# motorko_cryo_drake.net
KiCad netlist of a schematic drawn in EasyEDA Pro
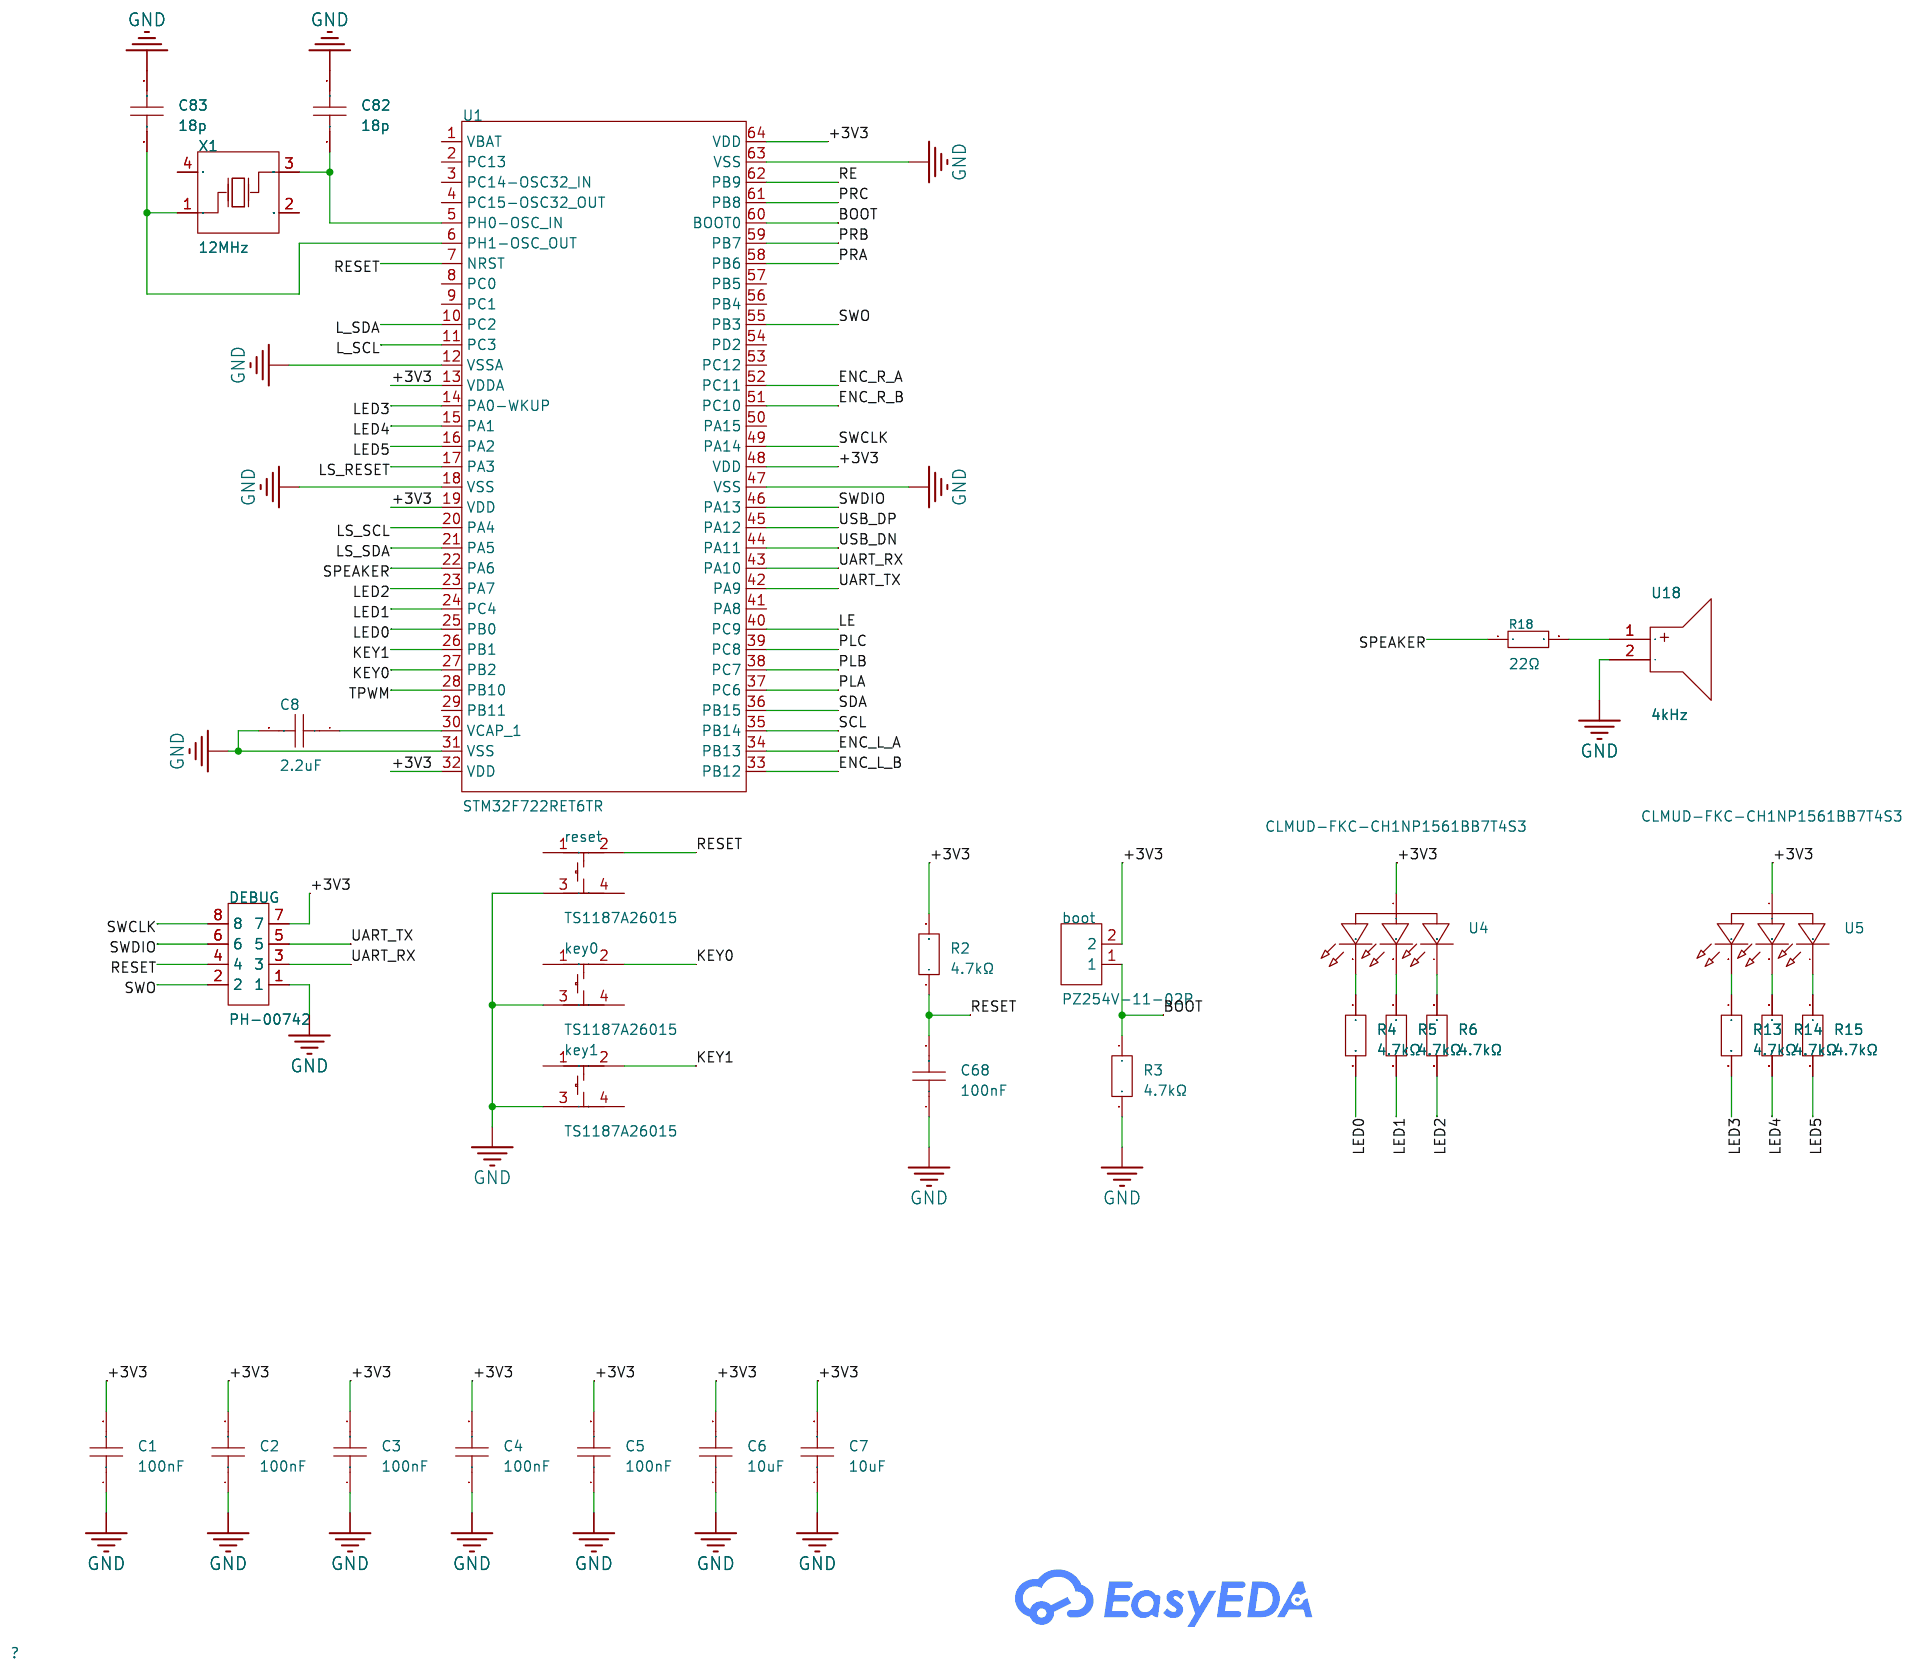
[diagram p0: main]
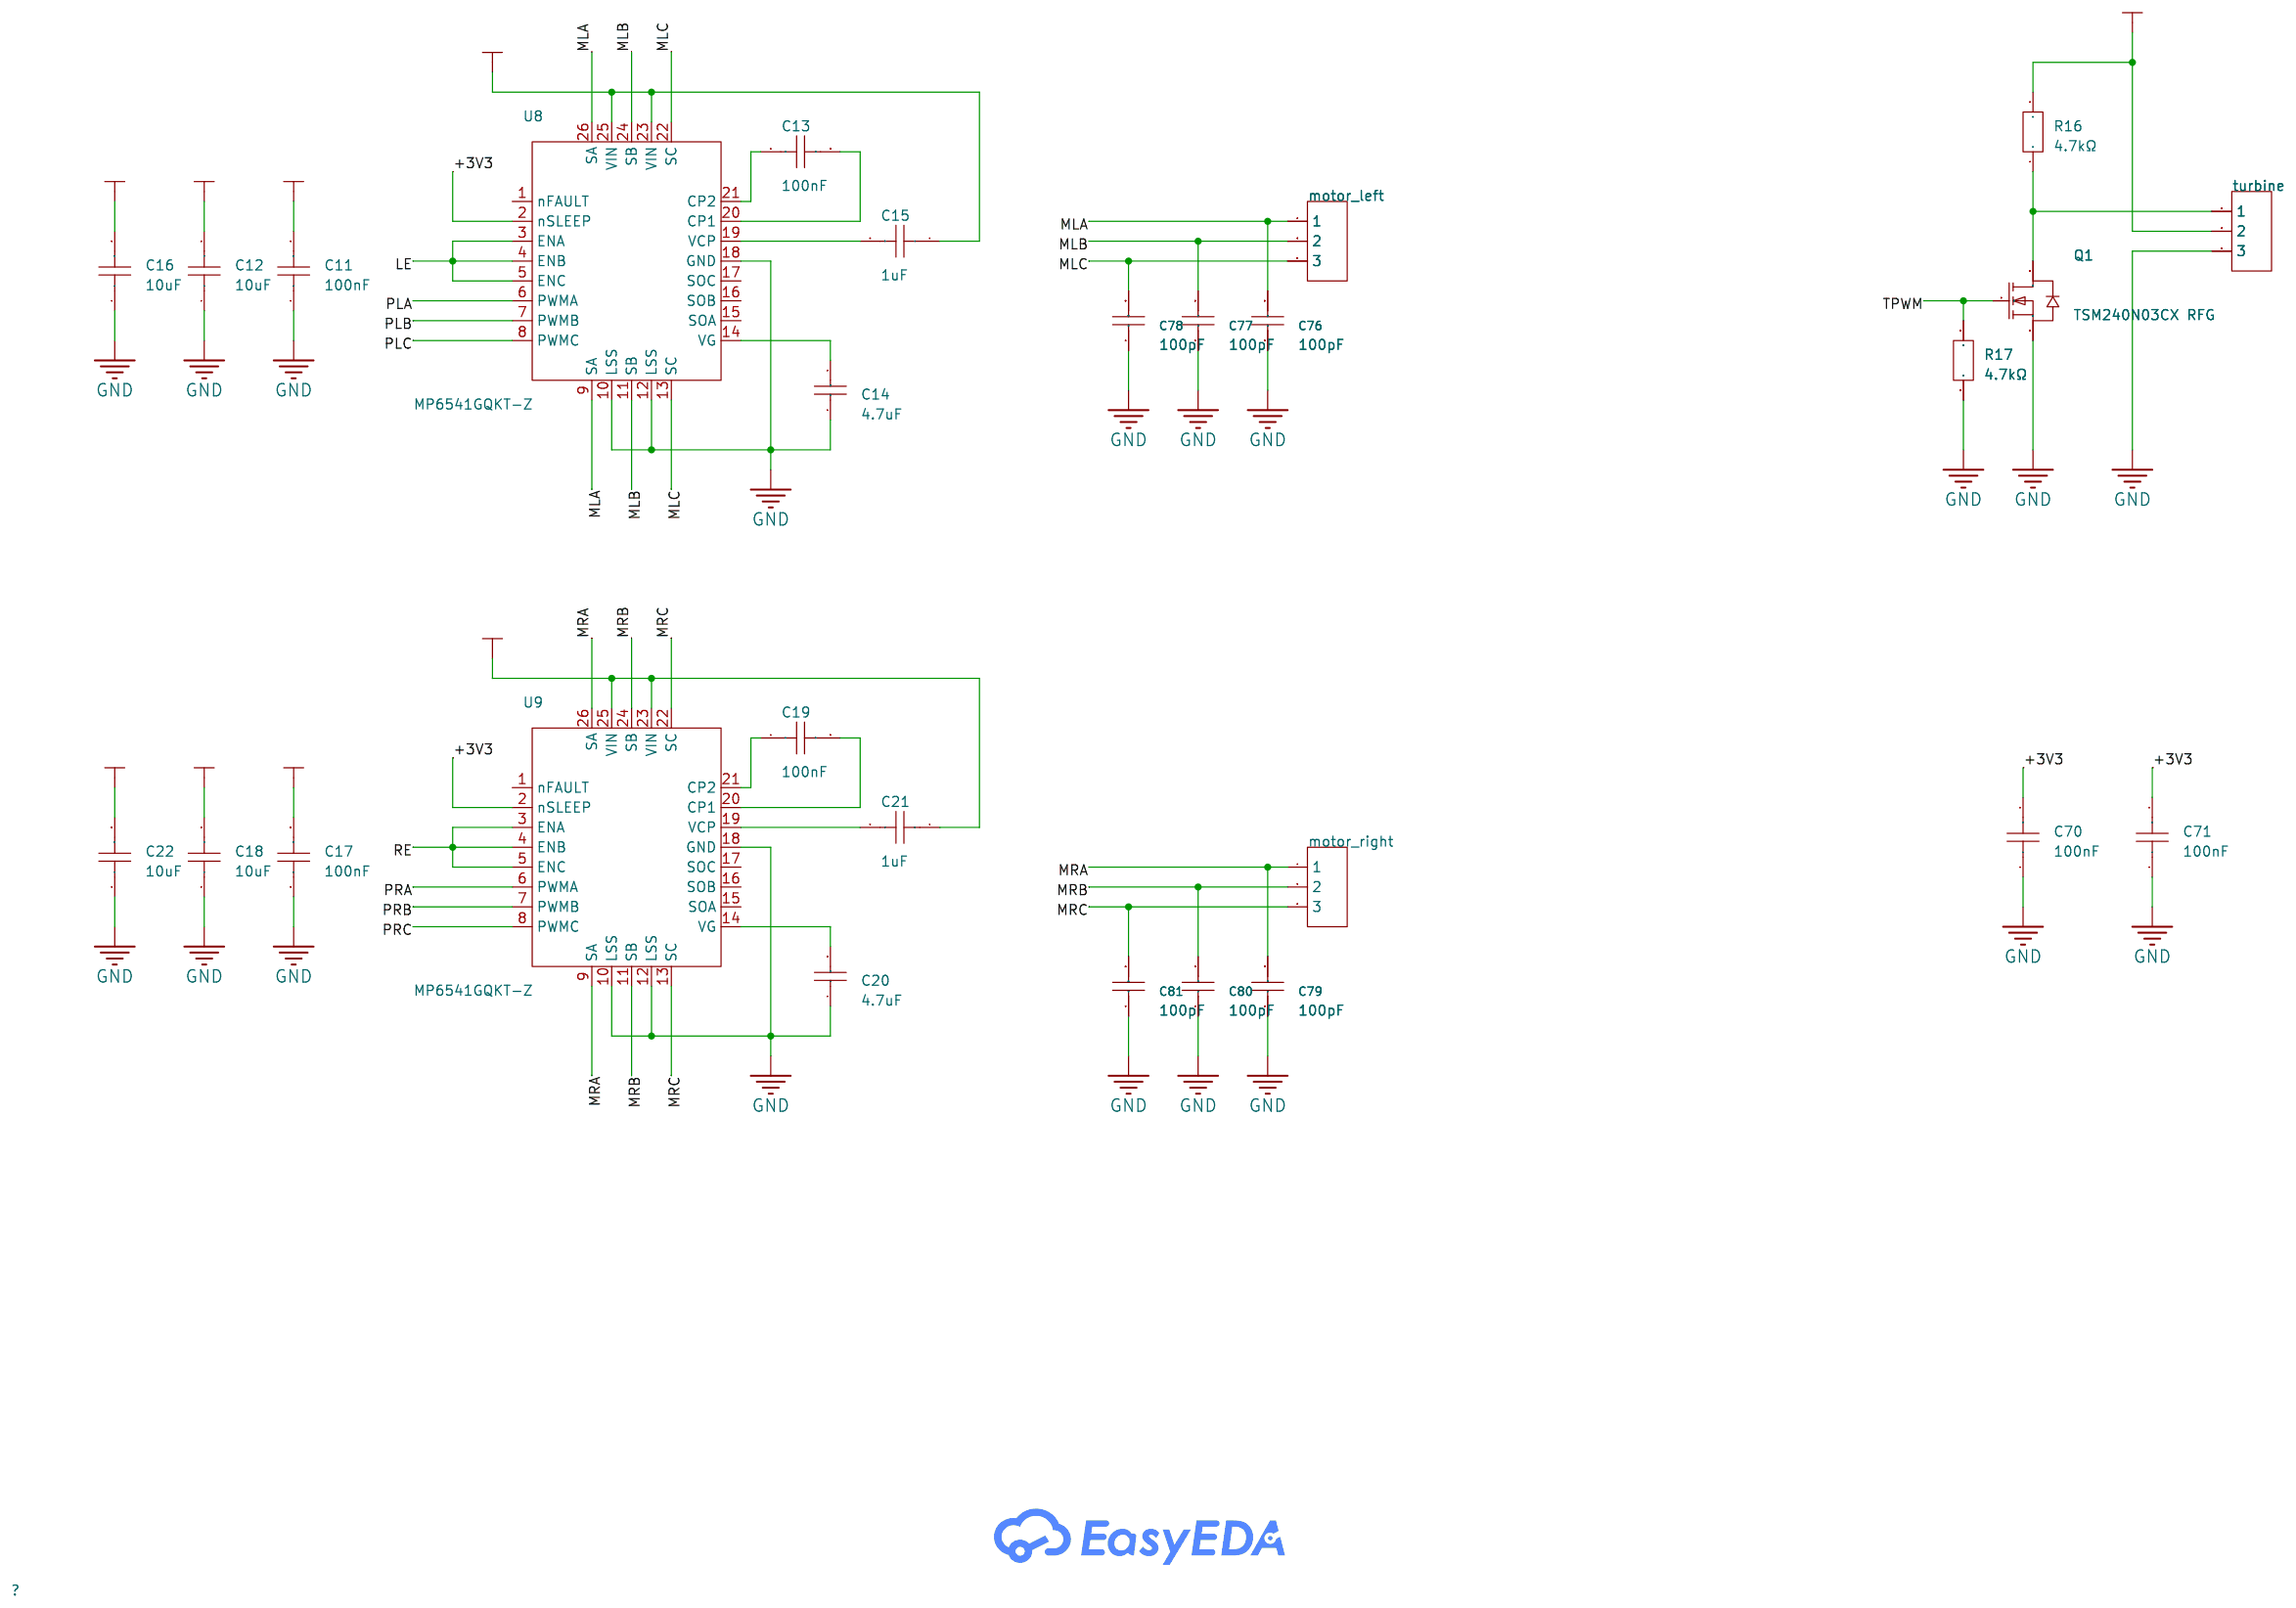
[diagram p1: motors]
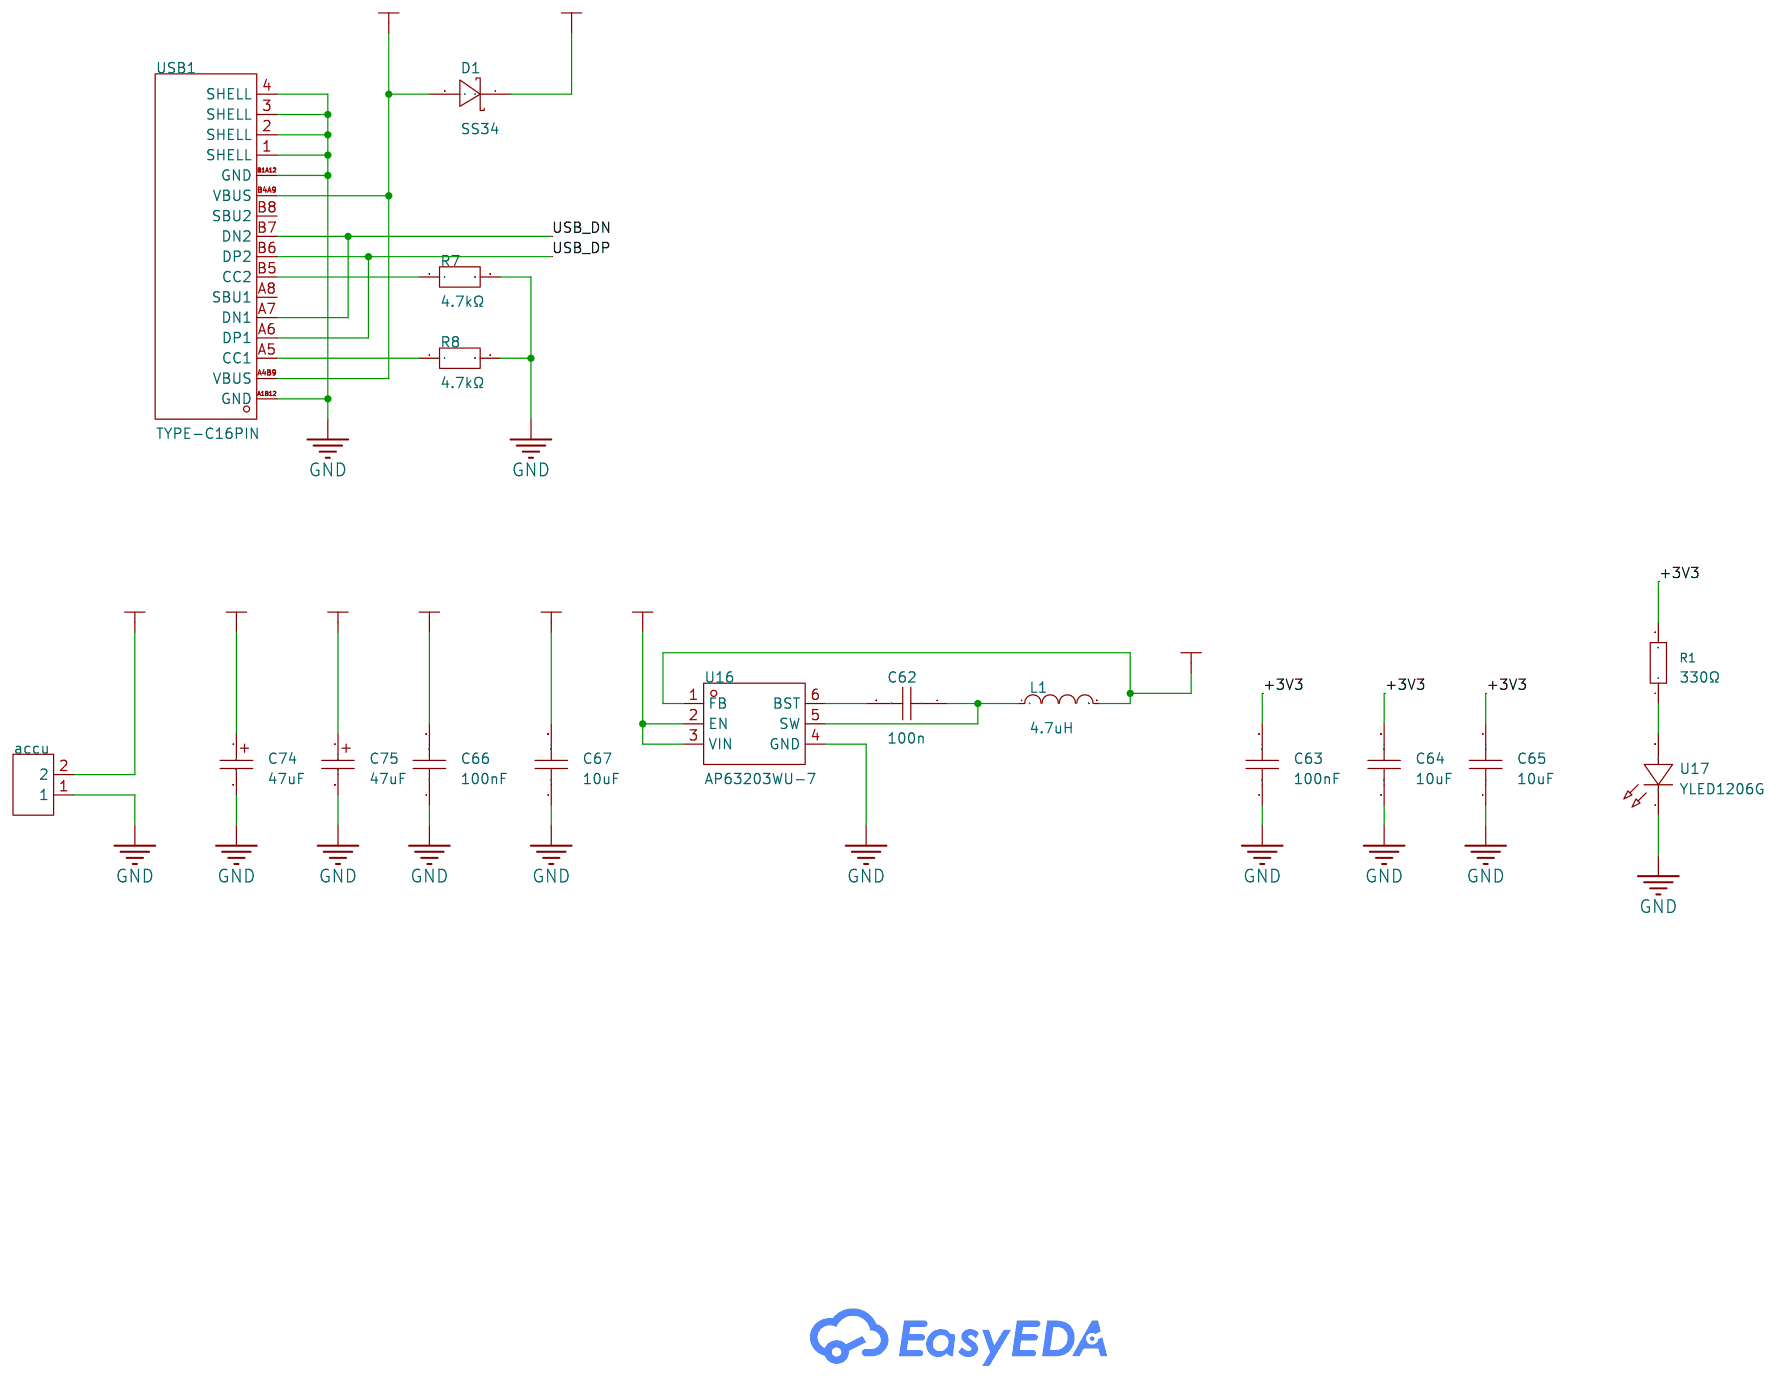
[diagram p2: power]
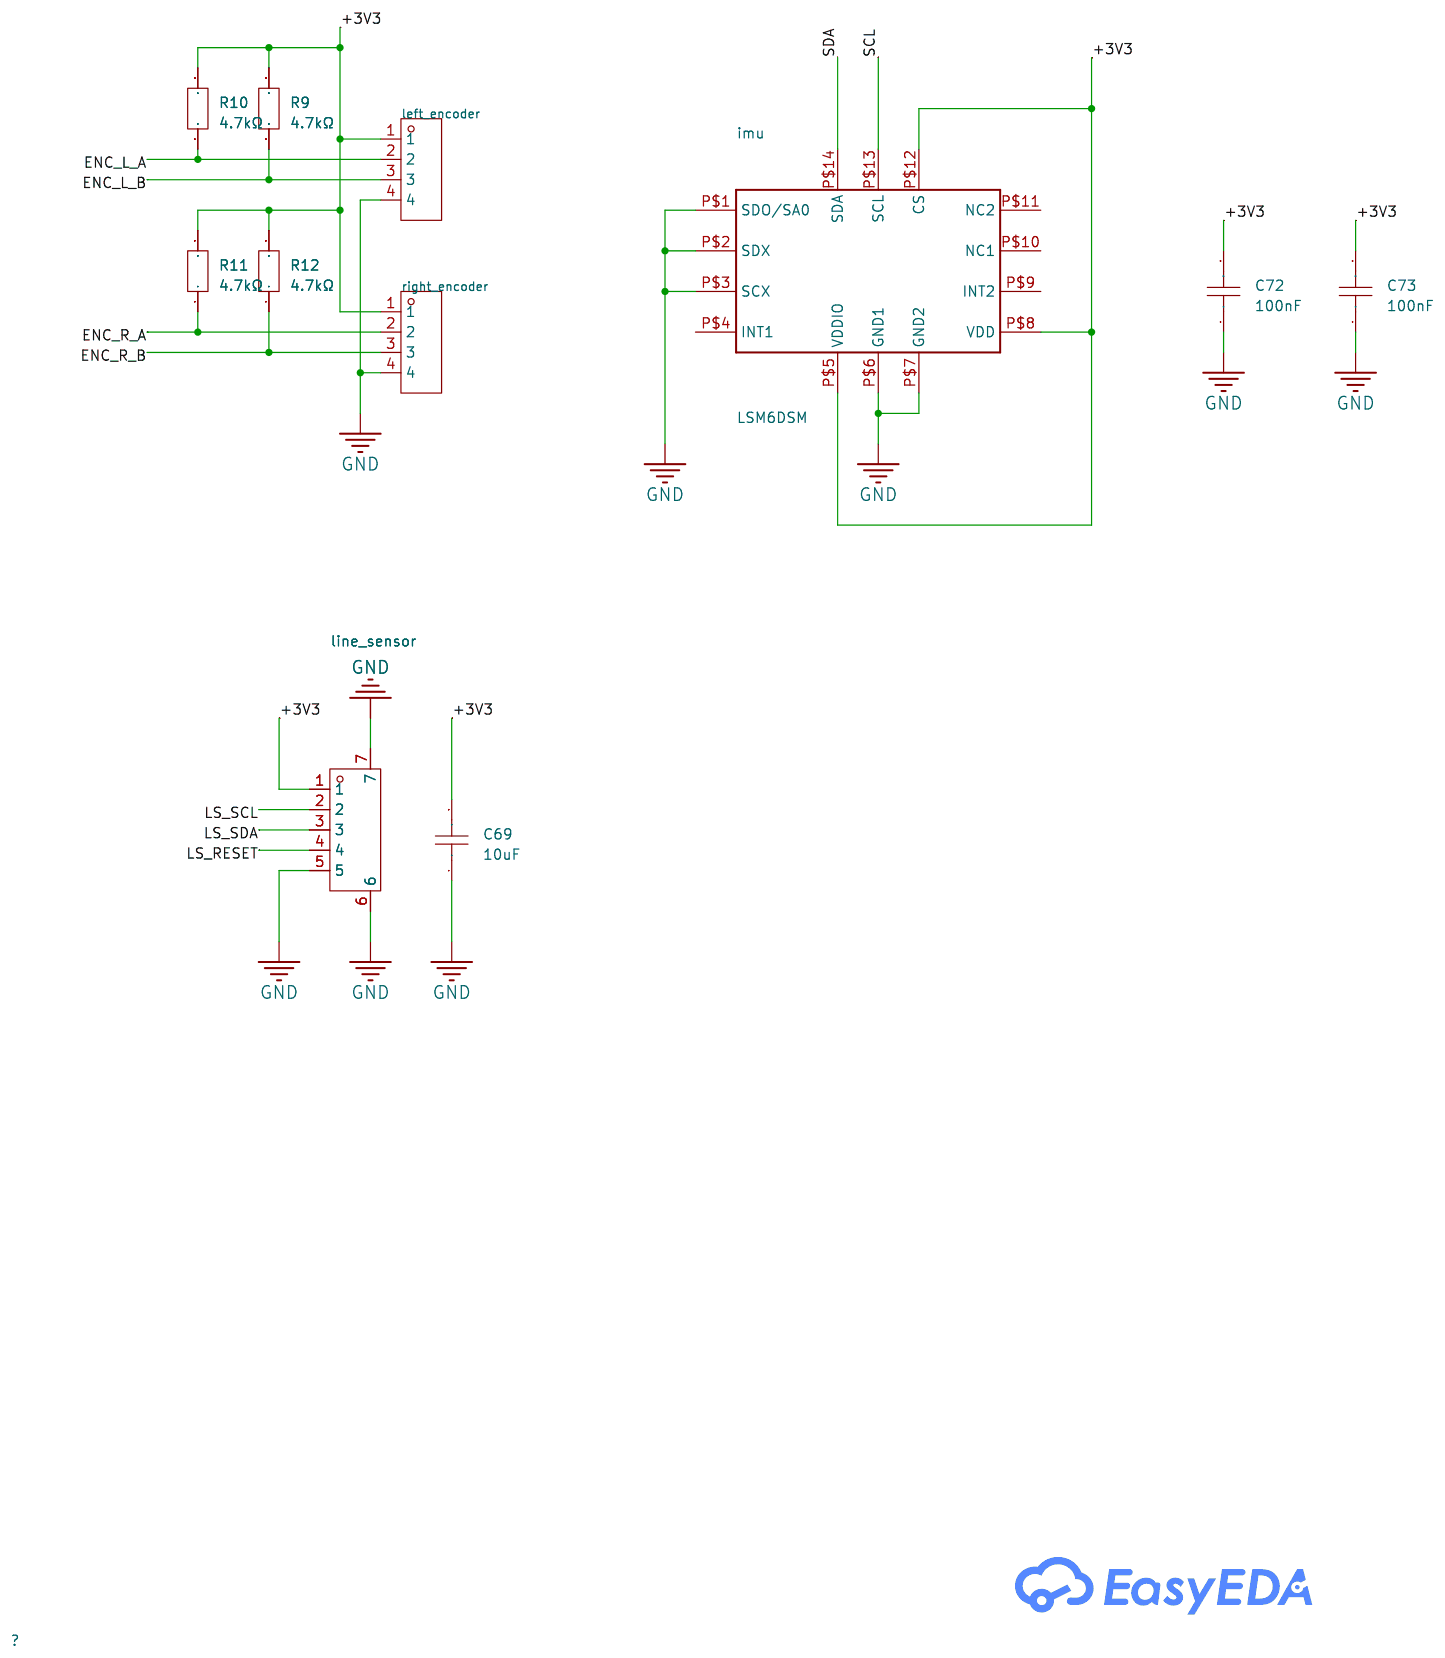
[diagram p3: sensors]

(export (version "E")
  (design (tool "Eeschema 10.0.6"))
  (components
    (comp (ref "boot")
      (value "PZ254V-11-02P")
      (footprint "easyedapro:HDR-TH_2P-P2.54-V-M")
      (fields (field (name "Manufacturer") "XFCN(兴飞)"))
      (libsource (lib "easyedapro") (part "PZ254V-11-02P"))
    )
    (comp (ref "C1")
      (value "100nF")
      (footprint "easyedapro:C0805")
      (description "Capacitance:100nF Tolerance:±10% Tolerance:±10% Voltage Rating:50V Temperature Coefficient:X7R")
      (fields
        (field (name "Manufacturer Part") "CC0805KRX7R9BB104")
        (field (name "Manufacturer") "YAGEO(国巨)")
      )
      (libsource (lib "easyedapro") (part "CC0805KRX7R9BB104"))
    )
    (comp (ref "C2")
      (value "100nF")
      (footprint "easyedapro:C0805")
      (description "Capacitance:100nF Tolerance:±10% Tolerance:±10% Voltage Rating:50V Temperature Coefficient:X7R")
      (fields
        (field (name "Manufacturer Part") "CC0805KRX7R9BB104")
        (field (name "Manufacturer") "YAGEO(国巨)")
      )
      (libsource (lib "easyedapro") (part "CC0805KRX7R9BB104"))
    )
    (comp (ref "C3")
      (value "100nF")
      (footprint "easyedapro:C0805")
      (description "Capacitance:100nF Tolerance:±10% Tolerance:±10% Voltage Rating:50V Temperature Coefficient:X7R")
      (fields
        (field (name "Manufacturer Part") "CC0805KRX7R9BB104")
        (field (name "Manufacturer") "YAGEO(国巨)")
      )
      (libsource (lib "easyedapro") (part "CC0805KRX7R9BB104"))
    )
    (comp (ref "C4")
      (value "100nF")
      (footprint "easyedapro:C0805")
      (description "Capacitance:100nF Tolerance:±10% Tolerance:±10% Voltage Rating:50V Temperature Coefficient:X7R")
      (fields
        (field (name "Manufacturer Part") "CC0805KRX7R9BB104")
        (field (name "Manufacturer") "YAGEO(国巨)")
      )
      (libsource (lib "easyedapro") (part "CC0805KRX7R9BB104"))
    )
    (comp (ref "C5")
      (value "100nF")
      (footprint "easyedapro:C0805")
      (description "Capacitance:100nF Tolerance:±10% Tolerance:±10% Voltage Rating:50V Temperature Coefficient:X7R")
      (fields
        (field (name "Manufacturer Part") "CC0805KRX7R9BB104")
        (field (name "Manufacturer") "YAGEO(国巨)")
      )
      (libsource (lib "easyedapro") (part "CC0805KRX7R9BB104"))
    )
    (comp (ref "C6")
      (value "10uF")
      (footprint "easyedapro:C0805")
      (description "Capacitance:10uF Tolerance:±10% Tolerance:±10% Voltage Rating:50V Temperature Coefficient:X5R")
      (fields
        (field (name "Manufacturer Part") "GRM21BR61H106KE43L")
        (field (name "Manufacturer") "muRata(村田)")
      )
      (libsource (lib "easyedapro") (part "GRM21BR61H106KE43L"))
    )
    (comp (ref "C7")
      (value "10uF")
      (footprint "easyedapro:C0805")
      (description "Capacitance:10uF Tolerance:±10% Tolerance:±10% Voltage Rating:50V Temperature Coefficient:X5R")
      (fields
        (field (name "Manufacturer Part") "GRM21BR61H106KE43L")
        (field (name "Manufacturer") "muRata(村田)")
      )
      (libsource (lib "easyedapro") (part "GRM21BR61H106KE43L"))
    )
    (comp (ref "C8")
      (value "2.2uF")
      (footprint "easyedapro:C0805")
      (description "Capacitance:2.2uF Tolerance:±10% Tolerance:±10% Voltage Rating:50V Temperature Coefficient:X5R")
      (fields
        (field (name "Manufacturer Part") "CL21A225KBQNNNE")
        (field (name "Manufacturer") "SAMSUNG(三星)")
      )
      (libsource (lib "easyedapro") (part "CL21A225KBQNNNE"))
    )
    (comp (ref "C68")
      (value "100nF")
      (footprint "easyedapro:C0805")
      (description "Capacitance:100nF Tolerance:±10% Tolerance:±10% Voltage Rating:50V Temperature Coefficient:X7R")
      (fields
        (field (name "Manufacturer Part") "CC0805KRX7R9BB104")
        (field (name "Manufacturer") "YAGEO(国巨)")
      )
      (libsource (lib "easyedapro") (part "CC0805KRX7R9BB104"))
    )
    (comp (ref "C82")
      (value "18p")
      (footprint "easyedapro:C0805")
      (description "Capacitance:2.2uF Tolerance:±10% Tolerance:±10% Voltage Rating:50V Temperature Coefficient:X5R")
      (fields
        (field (name "Manufacturer Part") "CL21A225KBQNNNE")
        (field (name "Manufacturer") "SAMSUNG(三星)")
      )
      (libsource (lib "easyedapro") (part "CL21A225KBQNNNE"))
    )
    (comp (ref "C83")
      (value "18p")
      (footprint "easyedapro:C0805")
      (description "Capacitance:2.2uF Tolerance:±10% Tolerance:±10% Voltage Rating:50V Temperature Coefficient:X5R")
      (fields
        (field (name "Manufacturer Part") "CL21A225KBQNNNE")
        (field (name "Manufacturer") "SAMSUNG(三星)")
      )
      (libsource (lib "easyedapro") (part "CL21A225KBQNNNE"))
    )
    (comp (ref "DEBUG")
      (value "PH-00742")
      (footprint "easyedapro:HDR-TH_8P-P1.27-V-M-R2-C4-S1.27")
      (fields (field (name "Manufacturer") "Liansheng(连盛)"))
      (libsource (lib "easyedapro") (part "PH-00742"))
    )
    (comp (ref "key0")
      (value "TS1187A26015")
      (footprint "easyedapro:SW-SMD_4P-L5.1-W5.1-P3.70-LS6.5-TL_H1.5")
      (fields (field (name "Manufacturer") "HanElectricity(瀚源)"))
      (libsource (lib "easyedapro") (part "TS-1187A26015"))
    )
    (comp (ref "key1")
      (value "TS1187A26015")
      (footprint "easyedapro:SW-SMD_4P-L5.1-W5.1-P3.70-LS6.5-TL_H1.5")
      (fields (field (name "Manufacturer") "HanElectricity(瀚源)"))
      (libsource (lib "easyedapro") (part "TS-1187A26015"))
    )
    (comp (ref "R2")
      (value "4.7kΩ")
      (footprint "easyedapro:R0805")
      (fields (field (name "Manufacturer Part") "FRC0805J472 TS") (field (name "Manufacturer") "FOJAN(富捷)"))
      (libsource (lib "easyedapro") (part "FRC0805J472 TS"))
    )
    (comp (ref "R3")
      (value "4.7kΩ")
      (footprint "easyedapro:R0805")
      (fields (field (name "Manufacturer Part") "FRC0805J472 TS") (field (name "Manufacturer") "FOJAN(富捷)"))
      (libsource (lib "easyedapro") (part "FRC0805J472 TS"))
    )
    (comp (ref "R4")
      (value "4.7kΩ")
      (footprint "easyedapro:R0805")
      (fields (field (name "Manufacturer Part") "FRC0805J472 TS") (field (name "Manufacturer") "FOJAN(富捷)"))
      (libsource (lib "easyedapro") (part "FRC0805J472 TS"))
    )
    (comp (ref "R5")
      (value "4.7kΩ")
      (footprint "easyedapro:R0805")
      (fields (field (name "Manufacturer Part") "FRC0805J472 TS") (field (name "Manufacturer") "FOJAN(富捷)"))
      (libsource (lib "easyedapro") (part "FRC0805J472 TS"))
    )
    (comp (ref "R6")
      (value "4.7kΩ")
      (footprint "easyedapro:R0805")
      (fields (field (name "Manufacturer Part") "FRC0805J472 TS") (field (name "Manufacturer") "FOJAN(富捷)"))
      (libsource (lib "easyedapro") (part "FRC0805J472 TS"))
    )
    (comp (ref "R13")
      (value "4.7kΩ")
      (footprint "easyedapro:R0805")
      (fields (field (name "Manufacturer Part") "FRC0805J472 TS") (field (name "Manufacturer") "FOJAN(富捷)"))
      (libsource (lib "easyedapro") (part "FRC0805J472 TS"))
    )
    (comp (ref "R14")
      (value "4.7kΩ")
      (footprint "easyedapro:R0805")
      (fields (field (name "Manufacturer Part") "FRC0805J472 TS") (field (name "Manufacturer") "FOJAN(富捷)"))
      (libsource (lib "easyedapro") (part "FRC0805J472 TS"))
    )
    (comp (ref "R15")
      (value "4.7kΩ")
      (footprint "easyedapro:R0805")
      (fields (field (name "Manufacturer Part") "FRC0805J472 TS") (field (name "Manufacturer") "FOJAN(富捷)"))
      (libsource (lib "easyedapro") (part "FRC0805J472 TS"))
    )
    (comp (ref "R18")
      (value "22Ω")
      (footprint "easyedapro:R0805")
      (fields
        (field (name "Manufacturer Part") "0805W8J0220T5E")
        (field (name "Manufacturer") "UNI-ROYAL(厚声)")
      )
      (libsource (lib "easyedapro") (part "0805W8J0220T5E"))
    )
    (comp (ref "reset")
      (value "TS1187A26015")
      (footprint "easyedapro:SW-SMD_4P-L5.1-W5.1-P3.70-LS6.5-TL_H1.5")
      (fields (field (name "Manufacturer") "HanElectricity(瀚源)"))
      (libsource (lib "easyedapro") (part "TS-1187A26015"))
    )
    (comp (ref "U1")
      (value "STM32F722RET6TR")
      (footprint "easyedapro:LQFP-64_L10.0-W10.0-P0.50-LS12.0-BL")
      (fields (field (name "Manufacturer") "ST(意法半导体)"))
      (libsource (lib "easyedapro") (part "STM32F722RET6TR"))
    )
    (comp (ref "U4")
      (value "CLMUD-FKC-CH1NP1561BB7T4S3")
      (footprint "easyedapro:LED-SMD_4P-L1.5-W1.5_CLMUD-FKC-CH1NP1561BB7T4S3")
      (description "Diode Configuration:Common Anode")
      (fields (field (name "Manufacturer") "CREE LED"))
      (libsource (lib "easyedapro") (part "CLMUD-FKC-CH1NP1561BB7T4S3"))
    )
    (comp (ref "U5")
      (value "CLMUD-FKC-CH1NP1561BB7T4S3")
      (footprint "easyedapro:LED-SMD_4P-L1.5-W1.5_CLMUD-FKC-CH1NP1561BB7T4S3")
      (description "Diode Configuration:Common Anode")
      (fields (field (name "Manufacturer") "CREE LED"))
      (libsource (lib "easyedapro") (part "CLMUD-FKC-CH1NP1561BB7T4S3"))
    )
    (comp (ref "U18")
      (value "4kHz")
      (footprint "easyedapro:BUZ-SMD_L4.0-W4.0-P3.50-L")
      (fields (field (name "Manufacturer Part") "SMT-0440-T-2-R") (field (name "Manufacturer") "PUIAUDIO"))
      (libsource (lib "easyedapro") (part "SMT-0440-T-2-R"))
    )
    (comp (ref "X1")
      (value "12MHz")
      (footprint "easyedapro:CRYSTAL-SMD_4P-L3.2-W2.5-BL")
      (fields (field (name "Manufacturer Part") "X322512MSB4SI") (field (name "Manufacturer") "YXC(扬兴晶振)"))
      (libsource (lib "easyedapro") (part "X322512MSB4SI"))
    )
    (comp (ref "C11")
      (value "100nF")
      (footprint "easyedapro:C0805")
      (description "Capacitance:100nF Tolerance:±10% Tolerance:±10% Voltage Rating:50V Temperature Coefficient:X7R")
      (fields
        (field (name "Manufacturer Part") "CC0805KRX7R9BB104")
        (field (name "Manufacturer") "YAGEO(国巨)")
      )
      (libsource (lib "easyedapro") (part "CC0805KRX7R9BB104"))
    )
    (comp (ref "C12")
      (value "10uF")
      (footprint "easyedapro:C0805")
      (description "Capacitance:10uF Tolerance:±10% Tolerance:±10% Voltage Rating:50V Temperature Coefficient:X5R")
      (fields
        (field (name "Manufacturer Part") "GRM21BR61H106KE43L")
        (field (name "Manufacturer") "muRata(村田)")
      )
      (libsource (lib "easyedapro") (part "GRM21BR61H106KE43L"))
    )
    (comp (ref "C13")
      (value "100nF")
      (footprint "easyedapro:C0805")
      (description "Capacitance:100nF Tolerance:±10% Tolerance:±10% Voltage Rating:50V Temperature Coefficient:X7R")
      (fields
        (field (name "Manufacturer Part") "CC0805KRX7R9BB104")
        (field (name "Manufacturer") "YAGEO(国巨)")
      )
      (libsource (lib "easyedapro") (part "CC0805KRX7R9BB104"))
    )
    (comp (ref "C14")
      (value "4.7uF")
      (footprint "easyedapro:C0805")
      (description "Capacitance:4.7uF Tolerance:±10% Tolerance:±10% Voltage Rating:25V Temperature Coefficient:X5R")
      (fields
        (field (name "Manufacturer Part") "CL21A475KAQNNNE")
        (field (name "Manufacturer") "SAMSUNG(三星)")
      )
      (libsource (lib "easyedapro") (part "CL21A475KAQNNNE"))
    )
    (comp (ref "C15")
      (value "1uF")
      (footprint "easyedapro:C0805")
      (description "Capacitance:1uF Tolerance:±20% Tolerance:±20% Voltage Rating:50V Temperature Coefficient:X7R")
      (fields
        (field (name "Manufacturer Part") "TCC0805X7R105M500FT")
        (field (name "Manufacturer") "CCTC(三环)")
      )
      (libsource (lib "easyedapro") (part "TCC0805X7R105M500FT"))
    )
    (comp (ref "C16")
      (value "10uF")
      (footprint "easyedapro:C0805")
      (description "Capacitance:10uF Tolerance:±10% Tolerance:±10% Voltage Rating:50V Temperature Coefficient:X5R")
      (fields
        (field (name "Manufacturer Part") "GRM21BR61H106KE43L")
        (field (name "Manufacturer") "muRata(村田)")
      )
      (libsource (lib "easyedapro") (part "GRM21BR61H106KE43L"))
    )
    (comp (ref "C17")
      (value "100nF")
      (footprint "easyedapro:C0805")
      (description "Capacitance:100nF Tolerance:±10% Tolerance:±10% Voltage Rating:50V Temperature Coefficient:X7R")
      (fields
        (field (name "Manufacturer Part") "CC0805KRX7R9BB104")
        (field (name "Manufacturer") "YAGEO(国巨)")
      )
      (libsource (lib "easyedapro") (part "CC0805KRX7R9BB104"))
    )
    (comp (ref "C18")
      (value "10uF")
      (footprint "easyedapro:C0805")
      (description "Capacitance:10uF Tolerance:±10% Tolerance:±10% Voltage Rating:50V Temperature Coefficient:X5R")
      (fields
        (field (name "Manufacturer Part") "GRM21BR61H106KE43L")
        (field (name "Manufacturer") "muRata(村田)")
      )
      (libsource (lib "easyedapro") (part "GRM21BR61H106KE43L"))
    )
    (comp (ref "C19")
      (value "100nF")
      (footprint "easyedapro:C0805")
      (description "Capacitance:100nF Tolerance:±10% Tolerance:±10% Voltage Rating:50V Temperature Coefficient:X7R")
      (fields
        (field (name "Manufacturer Part") "CC0805KRX7R9BB104")
        (field (name "Manufacturer") "YAGEO(国巨)")
      )
      (libsource (lib "easyedapro") (part "CC0805KRX7R9BB104"))
    )
    (comp (ref "C20")
      (value "4.7uF")
      (footprint "easyedapro:C0805")
      (description "Capacitance:4.7uF Tolerance:±10% Tolerance:±10% Voltage Rating:25V Temperature Coefficient:X5R")
      (fields
        (field (name "Manufacturer Part") "CL21A475KAQNNNE")
        (field (name "Manufacturer") "SAMSUNG(三星)")
      )
      (libsource (lib "easyedapro") (part "CL21A475KAQNNNE"))
    )
    (comp (ref "C21")
      (value "1uF")
      (footprint "easyedapro:C0805")
      (description "Capacitance:1uF Tolerance:±20% Tolerance:±20% Voltage Rating:50V Temperature Coefficient:X7R")
      (fields
        (field (name "Manufacturer Part") "TCC0805X7R105M500FT")
        (field (name "Manufacturer") "CCTC(三环)")
      )
      (libsource (lib "easyedapro") (part "TCC0805X7R105M500FT"))
    )
    (comp (ref "C22")
      (value "10uF")
      (footprint "easyedapro:C0805")
      (description "Capacitance:10uF Tolerance:±10% Tolerance:±10% Voltage Rating:50V Temperature Coefficient:X5R")
      (fields
        (field (name "Manufacturer Part") "GRM21BR61H106KE43L")
        (field (name "Manufacturer") "muRata(村田)")
      )
      (libsource (lib "easyedapro") (part "GRM21BR61H106KE43L"))
    )
    (comp (ref "C70")
      (value "100nF")
      (footprint "easyedapro:C0805")
      (description "Capacitance:100nF Tolerance:±10% Tolerance:±10% Voltage Rating:50V Temperature Coefficient:X7R")
      (fields
        (field (name "Manufacturer Part") "CC0805KRX7R9BB104")
        (field (name "Manufacturer") "YAGEO(国巨)")
      )
      (libsource (lib "easyedapro") (part "CC0805KRX7R9BB104"))
    )
    (comp (ref "C71")
      (value "100nF")
      (footprint "easyedapro:C0805")
      (description "Capacitance:100nF Tolerance:±10% Tolerance:±10% Voltage Rating:50V Temperature Coefficient:X7R")
      (fields
        (field (name "Manufacturer Part") "CC0805KRX7R9BB104")
        (field (name "Manufacturer") "YAGEO(国巨)")
      )
      (libsource (lib "easyedapro") (part "CC0805KRX7R9BB104"))
    )
    (comp (ref "C76")
      (value "100pF")
      (footprint "easyedapro:C0805")
      (description "Capacitance:100pF Tolerance:±5% Tolerance:±5% Voltage Rating:50V Temperature Coefficient:C0G")
      (fields
        (field (name "Manufacturer Part") "CL21C101JBANNNC")
        (field (name "Manufacturer") "SAMSUNG(三星)")
      )
      (libsource (lib "easyedapro") (part "CL21C101JBANNNC"))
    )
    (comp (ref "C77")
      (value "100pF")
      (footprint "easyedapro:C0805")
      (description "Capacitance:100pF Tolerance:±5% Tolerance:±5% Voltage Rating:50V Temperature Coefficient:C0G")
      (fields
        (field (name "Manufacturer Part") "CL21C101JBANNNC")
        (field (name "Manufacturer") "SAMSUNG(三星)")
      )
      (libsource (lib "easyedapro") (part "CL21C101JBANNNC"))
    )
    (comp (ref "C78")
      (value "100pF")
      (footprint "easyedapro:C0805")
      (description "Capacitance:100pF Tolerance:±5% Tolerance:±5% Voltage Rating:50V Temperature Coefficient:C0G")
      (fields
        (field (name "Manufacturer Part") "CL21C101JBANNNC")
        (field (name "Manufacturer") "SAMSUNG(三星)")
      )
      (libsource (lib "easyedapro") (part "CL21C101JBANNNC"))
    )
    (comp (ref "C79")
      (value "100pF")
      (footprint "easyedapro:C0805")
      (description "Capacitance:100pF Tolerance:±5% Tolerance:±5% Voltage Rating:50V Temperature Coefficient:C0G")
      (fields
        (field (name "Manufacturer Part") "CL21C101JBANNNC")
        (field (name "Manufacturer") "SAMSUNG(三星)")
      )
      (libsource (lib "easyedapro") (part "CL21C101JBANNNC"))
    )
    (comp (ref "C80")
      (value "100pF")
      (footprint "easyedapro:C0805")
      (description "Capacitance:100pF Tolerance:±5% Tolerance:±5% Voltage Rating:50V Temperature Coefficient:C0G")
      (fields
        (field (name "Manufacturer Part") "CL21C101JBANNNC")
        (field (name "Manufacturer") "SAMSUNG(三星)")
      )
      (libsource (lib "easyedapro") (part "CL21C101JBANNNC"))
    )
    (comp (ref "C81")
      (value "100pF")
      (footprint "easyedapro:C0805")
      (description "Capacitance:100pF Tolerance:±5% Tolerance:±5% Voltage Rating:50V Temperature Coefficient:C0G")
      (fields
        (field (name "Manufacturer Part") "CL21C101JBANNNC")
        (field (name "Manufacturer") "SAMSUNG(三星)")
      )
      (libsource (lib "easyedapro") (part "CL21C101JBANNNC"))
    )
    (comp (ref "motor_left")
      (value "2.54-1*3P针")
      (footprint "easyedapro:HDR-TH_3P-P2.54-V-M-1")
      (fields (field (name "Manufacturer") "BOOMELE(博穆精密)"))
      (libsource (lib "easyedapro") (part "Header-Male-2.54_1x3"))
    )
    (comp (ref "motor_right")
      (value "2.54-1*3P针")
      (footprint "easyedapro:HDR-TH_3P-P2.54-V-M-1")
      (fields (field (name "Manufacturer") "BOOMELE(博穆精密)"))
      (libsource (lib "easyedapro") (part "Header-Male-2.54_1x3"))
    )
    (comp (ref "Q1")
      (value "TSM240N03CX RFG")
      (footprint "easyedapro:SOT-23-3_L2.9-W1.6-P1.90-LS2.8-BR")
      (fields (field (name "Manufacturer") "Taiwan Semiconductor(台湾半导体)"))
      (libsource (lib "easyedapro") (part "TSM240N03CX RFG"))
    )
    (comp (ref "R16")
      (value "4.7kΩ")
      (footprint "easyedapro:R0805")
      (fields (field (name "Manufacturer Part") "FRC0805J472 TS") (field (name "Manufacturer") "FOJAN(富捷)"))
      (libsource (lib "easyedapro") (part "FRC0805J472 TS"))
    )
    (comp (ref "R17")
      (value "4.7kΩ")
      (footprint "easyedapro:R0805")
      (fields (field (name "Manufacturer Part") "FRC0805J472 TS") (field (name "Manufacturer") "FOJAN(富捷)"))
      (libsource (lib "easyedapro") (part "FRC0805J472 TS"))
    )
    (comp (ref "turbine")
      (value "2.54-1*3P针")
      (footprint "easyedapro:HDR-TH_3P-P2.54-V-M-1")
      (fields (field (name "Manufacturer") "BOOMELE(博穆精密)"))
      (libsource (lib "easyedapro") (part "Header-Male-2.54_1x3"))
    )
    (comp (ref "U8")
      (value "MP6541GQKT-Z")
      (footprint "easyedapro:QFN-26_L6.0-W6.0-P0.65-TL_MP6541")
      (fields (field (name "Manufacturer") "MPS(芯源)"))
      (libsource (lib "easyedapro") (part "MP6541GQKT-Z"))
    )
    (comp (ref "U9")
      (value "MP6541GQKT-Z")
      (footprint "easyedapro:QFN-26_L6.0-W6.0-P0.65-TL_MP6541")
      (fields (field (name "Manufacturer") "MPS(芯源)"))
      (libsource (lib "easyedapro") (part "MP6541GQKT-Z"))
    )
    (comp (ref "accu")
      (value "PZ254V-11-02P")
      (footprint "easyedapro:HDR-TH_2P-P2.54-V-M")
      (fields (field (name "Manufacturer") "XFCN(兴飞)"))
      (libsource (lib "easyedapro") (part "PZ254V-11-02P"))
    )
    (comp (ref "C62")
      (value "100n")
      (footprint "easyedapro:C0805")
      (description "Capacitance:10uF Tolerance:±10% Tolerance:±10% Voltage Rating:25V Temperature Coefficient:X5R")
      (fields
        (field (name "Manufacturer Part") "CL21A106KAYNNNE")
        (field (name "Manufacturer") "SAMSUNG(三星)")
      )
      (libsource (lib "easyedapro") (part "CL21A106KAYNNNE"))
    )
    (comp (ref "C63")
      (value "100nF")
      (footprint "easyedapro:C0805")
      (description "Capacitance:100nF Tolerance:±10% Tolerance:±10% Voltage Rating:50V Temperature Coefficient:X7R")
      (fields
        (field (name "Manufacturer Part") "CC0805KRX7R9BB104")
        (field (name "Manufacturer") "YAGEO(国巨)")
      )
      (libsource (lib "easyedapro") (part "CC0805KRX7R9BB104"))
    )
    (comp (ref "C64")
      (value "10uF")
      (footprint "easyedapro:C0805")
      (description "Capacitance:10uF Tolerance:±10% Tolerance:±10% Voltage Rating:50V Temperature Coefficient:X5R")
      (fields
        (field (name "Manufacturer Part") "GRM21BR61H106KE43L")
        (field (name "Manufacturer") "muRata(村田)")
      )
      (libsource (lib "easyedapro") (part "GRM21BR61H106KE43L"))
    )
    (comp (ref "C65")
      (value "10uF")
      (footprint "easyedapro:C0805")
      (description "Capacitance:10uF Tolerance:±10% Tolerance:±10% Voltage Rating:50V Temperature Coefficient:X5R")
      (fields
        (field (name "Manufacturer Part") "GRM21BR61H106KE43L")
        (field (name "Manufacturer") "muRata(村田)")
      )
      (libsource (lib "easyedapro") (part "GRM21BR61H106KE43L"))
    )
    (comp (ref "C66")
      (value "100nF")
      (footprint "easyedapro:C0805")
      (description "Capacitance:100nF Tolerance:±10% Tolerance:±10% Voltage Rating:50V Temperature Coefficient:X7R")
      (fields
        (field (name "Manufacturer Part") "CC0805KRX7R9BB104")
        (field (name "Manufacturer") "YAGEO(国巨)")
      )
      (libsource (lib "easyedapro") (part "CC0805KRX7R9BB104"))
    )
    (comp (ref "C67")
      (value "10uF")
      (footprint "easyedapro:C0805")
      (description "Capacitance:10uF Tolerance:±10% Tolerance:±10% Voltage Rating:50V Temperature Coefficient:X5R")
      (fields
        (field (name "Manufacturer Part") "GRM21BR61H106KE43L")
        (field (name "Manufacturer") "muRata(村田)")
      )
      (libsource (lib "easyedapro") (part "GRM21BR61H106KE43L"))
    )
    (comp (ref "C74")
      (value "47uF")
      (footprint "easyedapro:CAP-SMD_L3.5-W2.8-R-RD")
      (fields (field (name "Manufacturer Part") "CA45-B010K476T") (field (name "Manufacturer") "湘怡中元/湘江"))
      (libsource (lib "easyedapro") (part "CA45-B010K476T"))
    )
    (comp (ref "C75")
      (value "47uF")
      (footprint "easyedapro:CAP-SMD_L3.5-W2.8-R-RD")
      (fields (field (name "Manufacturer Part") "CA45-B010K476T") (field (name "Manufacturer") "湘怡中元/湘江"))
      (libsource (lib "easyedapro") (part "CA45-B010K476T"))
    )
    (comp (ref "D1")
      (value "SS34")
      (footprint "easyedapro:SMA_L4.3-W2.6-LS5.2-RD")
      (fields (field (name "Manufacturer") "MDD(辰达半导体)"))
      (libsource (lib "easyedapro") (part "SS34_C8678"))
    )
    (comp (ref "L1")
      (value "4.7uH")
      (footprint "easyedapro:IND-SMD_L4.0-W4.0_FNR40XXS")
      (fields (field (name "Manufacturer Part") "FNR4030S4R7MT") (field (name "Manufacturer") "cjiang(长江微电)"))
      (libsource (lib "easyedapro") (part "FNR4030S4R7MT"))
    )
    (comp (ref "R1")
      (value "330Ω")
      (footprint "easyedapro:R0805")
      (fields
        (field (name "Manufacturer Part") "0805W8F3300T5E")
        (field (name "Manufacturer") "UNI-ROYAL(厚声)")
      )
      (libsource (lib "easyedapro") (part "0805W8F3300T5E"))
    )
    (comp (ref "R7")
      (value "4.7kΩ")
      (footprint "easyedapro:R0805")
      (fields (field (name "Manufacturer Part") "FRC0805J472 TS") (field (name "Manufacturer") "FOJAN(富捷)"))
      (libsource (lib "easyedapro") (part "FRC0805J472 TS"))
    )
    (comp (ref "R8")
      (value "4.7kΩ")
      (footprint "easyedapro:R0805")
      (fields (field (name "Manufacturer Part") "FRC0805J472 TS") (field (name "Manufacturer") "FOJAN(富捷)"))
      (libsource (lib "easyedapro") (part "FRC0805J472 TS"))
    )
    (comp (ref "U16")
      (value "AP63203WU-7")
      (footprint "easyedapro:TSOT-26_L2.9-W1.6-P0.95-LS2.8-BL")
      (fields (field (name "Manufacturer") "DIODES(美台)"))
      (libsource (lib "easyedapro") (part "AP63203WU-7"))
    )
    (comp (ref "U17")
      (value "YLED1206G")
      (footprint "easyedapro:LED1206-RD")
      (fields (field (name "Manufacturer") "YONGYUTAI(永裕泰)"))
      (libsource (lib "easyedapro") (part "YLED1206G"))
    )
    (comp (ref "USB1")
      (value "TYPE-C16PIN")
      (footprint "easyedapro:USB-C-SMD_TYPE-C16PIN")
      (fields (field (name "Manufacturer") "SHOU HAN(首韩)"))
      (libsource (lib "easyedapro") (part "TYPE-C16PIN"))
    )
    (comp (ref "C69")
      (value "10uF")
      (footprint "easyedapro:C0805")
      (description "Capacitance:10uF Tolerance:±10% Tolerance:±10% Voltage Rating:50V Temperature Coefficient:X5R")
      (fields
        (field (name "Manufacturer Part") "GRM21BR61H106KE43L")
        (field (name "Manufacturer") "muRata(村田)")
      )
      (libsource (lib "easyedapro") (part "GRM21BR61H106KE43L"))
    )
    (comp (ref "C72")
      (value "100nF")
      (footprint "easyedapro:C0805")
      (description "Capacitance:100nF Tolerance:±10% Tolerance:±10% Voltage Rating:50V Temperature Coefficient:X7R")
      (fields
        (field (name "Manufacturer Part") "CC0805KRX7R9BB104")
        (field (name "Manufacturer") "YAGEO(国巨)")
      )
      (libsource (lib "easyedapro") (part "CC0805KRX7R9BB104"))
    )
    (comp (ref "C73")
      (value "100nF")
      (footprint "easyedapro:C0805")
      (description "Capacitance:100nF Tolerance:±10% Tolerance:±10% Voltage Rating:50V Temperature Coefficient:X7R")
      (fields
        (field (name "Manufacturer Part") "CC0805KRX7R9BB104")
        (field (name "Manufacturer") "YAGEO(国巨)")
      )
      (libsource (lib "easyedapro") (part "CC0805KRX7R9BB104"))
    )
    (comp (ref "imu")
      (value "LSM6DSM")
      (footprint "easyedapro:LGA14L")
      (libsource (lib "easyedapro") (part "LSM6DSM"))
    )
    (comp (ref "left_encoder")
      (value "PZ254V-11-04P")
      (footprint "easyedapro:HDR-TH_4P-P2.54-V-M")
      (fields (field (name "Manufacturer") "XFCN(兴飞)"))
      (libsource (lib "easyedapro") (part "PZ254V-11-04P_C2691448"))
    )
    (comp (ref "line_sensor")
      (value "GT-F0509SR15-05SMT01")
      (footprint "easyedapro:CONN-SMD_GT-F0509SR15-05SMT01")
      (fields (field (name "Manufacturer") "G-Switch(品赞)"))
      (libsource (lib "easyedapro") (part "GT-F0509SR15-05SMT01"))
    )
    (comp (ref "R9")
      (value "4.7kΩ")
      (footprint "easyedapro:R0805")
      (fields (field (name "Manufacturer Part") "FRC0805J472 TS") (field (name "Manufacturer") "FOJAN(富捷)"))
      (libsource (lib "easyedapro") (part "FRC0805J472 TS"))
    )
    (comp (ref "R10")
      (value "4.7kΩ")
      (footprint "easyedapro:R0805")
      (fields (field (name "Manufacturer Part") "FRC0805J472 TS") (field (name "Manufacturer") "FOJAN(富捷)"))
      (libsource (lib "easyedapro") (part "FRC0805J472 TS"))
    )
    (comp (ref "R11")
      (value "4.7kΩ")
      (footprint "easyedapro:R0805")
      (fields (field (name "Manufacturer Part") "FRC0805J472 TS") (field (name "Manufacturer") "FOJAN(富捷)"))
      (libsource (lib "easyedapro") (part "FRC0805J472 TS"))
    )
    (comp (ref "R12")
      (value "4.7kΩ")
      (footprint "easyedapro:R0805")
      (fields (field (name "Manufacturer Part") "FRC0805J472 TS") (field (name "Manufacturer") "FOJAN(富捷)"))
      (libsource (lib "easyedapro") (part "FRC0805J472 TS"))
    )
    (comp (ref "right_encoder")
      (value "PZ254V-11-04P")
      (footprint "easyedapro:HDR-TH_4P-P2.54-V-M")
      (fields (field (name "Manufacturer") "XFCN(兴飞)"))
      (libsource (lib "easyedapro") (part "PZ254V-11-04P_C2691448"))
    )
  )
  (nets
    (net (code "1") (name "+3V3") (class "Default")
      (node (ref "C1") (pin "2") (pinfunction "2_2") (pintype "unspecified"))
      (node (ref "C2") (pin "2") (pinfunction "2_2") (pintype "unspecified"))
      (node (ref "C3") (pin "2") (pinfunction "2_2") (pintype "unspecified"))
      (node (ref "C4") (pin "2") (pinfunction "2_2") (pintype "unspecified"))
      (node (ref "C5") (pin "2") (pinfunction "2_2") (pintype "unspecified"))
      (node (ref "C6") (pin "2") (pinfunction "2_2") (pintype "unspecified"))
      (node (ref "C63") (pin "2") (pinfunction "2_2") (pintype "unspecified"))
      (node (ref "C64") (pin "2") (pinfunction "2_2") (pintype "unspecified"))
      (node (ref "C65") (pin "2") (pinfunction "2_2") (pintype "unspecified"))
      (node (ref "C69") (pin "2") (pinfunction "2_2") (pintype "unspecified"))
      (node (ref "C7") (pin "2") (pinfunction "2_2") (pintype "unspecified"))
      (node (ref "C70") (pin "2") (pinfunction "2_2") (pintype "unspecified"))
      (node (ref "C71") (pin "2") (pinfunction "2_2") (pintype "unspecified"))
      (node (ref "C72") (pin "2") (pinfunction "2_2") (pintype "unspecified"))
      (node (ref "C73") (pin "2") (pinfunction "2_2") (pintype "unspecified"))
      (node (ref "DEBUG") (pin "7") (pinfunction "7_7") (pintype "unspecified"))
      (node (ref "L1") (pin "2") (pinfunction "2_2") (pintype "unspecified"))
      (node (ref "R1") (pin "2") (pinfunction "2_2") (pintype "input"))
      (node (ref "R10") (pin "2") (pinfunction "2_2") (pintype "unspecified"))
      (node (ref "R11") (pin "2") (pinfunction "2_2") (pintype "unspecified"))
      (node (ref "R12") (pin "2") (pinfunction "2_2") (pintype "unspecified"))
      (node (ref "R2") (pin "2") (pinfunction "2_2") (pintype "unspecified"))
      (node (ref "R9") (pin "2") (pinfunction "2_2") (pintype "unspecified"))
      (node (ref "U1") (pin "13") (pinfunction "VDDA_13") (pintype "unspecified"))
      (node (ref "U1") (pin "19") (pinfunction "VDD_19") (pintype "unspecified"))
      (node (ref "U1") (pin "32") (pinfunction "VDD_32") (pintype "unspecified"))
      (node (ref "U1") (pin "48") (pinfunction "VDD_48") (pintype "unspecified"))
      (node (ref "U1") (pin "64") (pinfunction "VDD_64") (pintype "unspecified"))
      (node (ref "U16") (pin "1") (pinfunction "FB_1") (pintype "unspecified"))
      (node (ref "U4") (pin "1") (pinfunction "A_1") (pintype "unspecified"))
      (node (ref "U5") (pin "1") (pinfunction "A_1") (pintype "unspecified"))
      (node (ref "U8") (pin "2") (pinfunction "nSLEEP_2") (pintype "unspecified"))
      (node (ref "U9") (pin "2") (pinfunction "nSLEEP_2") (pintype "unspecified"))
      (node (ref "boot") (pin "2") (pinfunction "2_2") (pintype "unspecified"))
      (node (ref "imu") (pin "P$12") (pinfunction "CS_P$12") (pintype "bidirectional"))
      (node (ref "imu") (pin "P$5") (pinfunction "VDDIO_P$5") (pintype "bidirectional"))
      (node (ref "imu") (pin "P$8") (pinfunction "VDD_P$8") (pintype "bidirectional"))
      (node (ref "left_encoder") (pin "1") (pinfunction "1_1") (pintype "input"))
      (node (ref "line_sensor") (pin "1") (pinfunction "1_1") (pintype "unspecified"))
      (node (ref "right_encoder") (pin "1") (pinfunction "1_1") (pintype "input"))
    )
    (net (code "2") (name "BOOT") (class "Default")
      (node (ref "R3") (pin "1") (pinfunction "1_1") (pintype "unspecified"))
      (node (ref "U1") (pin "60") (pinfunction "BOOT0_60") (pintype "unspecified"))
      (node (ref "boot") (pin "1") (pinfunction "1_1") (pintype "unspecified"))
    )
    (net (code "3") (name "ENC_L_A") (class "Default")
      (node (ref "R10") (pin "1") (pinfunction "1_1") (pintype "unspecified"))
      (node (ref "U1") (pin "34") (pinfunction "PB13_34") (pintype "unspecified"))
      (node (ref "left_encoder") (pin "2") (pinfunction "2_2") (pintype "input"))
    )
    (net (code "4") (name "ENC_L_B") (class "Default")
      (node (ref "R9") (pin "1") (pinfunction "1_1") (pintype "unspecified"))
      (node (ref "U1") (pin "33") (pinfunction "PB12_33") (pintype "unspecified"))
      (node (ref "left_encoder") (pin "3") (pinfunction "3_3") (pintype "input"))
    )
    (net (code "5") (name "ENC_R_A") (class "Default")
      (node (ref "R11") (pin "1") (pinfunction "1_1") (pintype "unspecified"))
      (node (ref "U1") (pin "52") (pinfunction "PC11_52") (pintype "unspecified"))
      (node (ref "right_encoder") (pin "2") (pinfunction "2_2") (pintype "input"))
    )
    (net (code "6") (name "ENC_R_B") (class "Default")
      (node (ref "R12") (pin "1") (pinfunction "1_1") (pintype "unspecified"))
      (node (ref "U1") (pin "51") (pinfunction "PC10_51") (pintype "unspecified"))
      (node (ref "right_encoder") (pin "3") (pinfunction "3_3") (pintype "input"))
    )
    (net (code "7") (name "GND") (class "Default")
      (node (ref "C1") (pin "1") (pinfunction "1_1") (pintype "unspecified"))
      (node (ref "C11") (pin "1") (pinfunction "1_1") (pintype "unspecified"))
      (node (ref "C12") (pin "1") (pinfunction "1_1") (pintype "unspecified"))
      (node (ref "C14") (pin "1") (pinfunction "1_1") (pintype "input"))
      (node (ref "C16") (pin "1") (pinfunction "1_1") (pintype "unspecified"))
      (node (ref "C17") (pin "1") (pinfunction "1_1") (pintype "unspecified"))
      (node (ref "C18") (pin "1") (pinfunction "1_1") (pintype "unspecified"))
      (node (ref "C2") (pin "1") (pinfunction "1_1") (pintype "unspecified"))
      (node (ref "C20") (pin "1") (pinfunction "1_1") (pintype "input"))
      (node (ref "C22") (pin "1") (pinfunction "1_1") (pintype "unspecified"))
      (node (ref "C3") (pin "1") (pinfunction "1_1") (pintype "unspecified"))
      (node (ref "C4") (pin "1") (pinfunction "1_1") (pintype "unspecified"))
      (node (ref "C5") (pin "1") (pinfunction "1_1") (pintype "unspecified"))
      (node (ref "C6") (pin "1") (pinfunction "1_1") (pintype "unspecified"))
      (node (ref "C63") (pin "1") (pinfunction "1_1") (pintype "unspecified"))
      (node (ref "C64") (pin "1") (pinfunction "1_1") (pintype "unspecified"))
      (node (ref "C65") (pin "1") (pinfunction "1_1") (pintype "unspecified"))
      (node (ref "C66") (pin "1") (pinfunction "1_1") (pintype "unspecified"))
      (node (ref "C67") (pin "1") (pinfunction "1_1") (pintype "unspecified"))
      (node (ref "C68") (pin "1") (pinfunction "1_1") (pintype "unspecified"))
      (node (ref "C69") (pin "1") (pinfunction "1_1") (pintype "unspecified"))
      (node (ref "C7") (pin "1") (pinfunction "1_1") (pintype "unspecified"))
      (node (ref "C70") (pin "1") (pinfunction "1_1") (pintype "unspecified"))
      (node (ref "C71") (pin "1") (pinfunction "1_1") (pintype "unspecified"))
      (node (ref "C72") (pin "1") (pinfunction "1_1") (pintype "unspecified"))
      (node (ref "C73") (pin "1") (pinfunction "1_1") (pintype "unspecified"))
      (node (ref "C74") (pin "2") (pinfunction "2_2") (pintype "input"))
      (node (ref "C75") (pin "2") (pinfunction "2_2") (pintype "input"))
      (node (ref "C76") (pin "1") (pinfunction "1_1") (pintype "input"))
      (node (ref "C77") (pin "1") (pinfunction "1_1") (pintype "input"))
      (node (ref "C78") (pin "1") (pinfunction "1_1") (pintype "input"))
      (node (ref "C79") (pin "1") (pinfunction "1_1") (pintype "input"))
      (node (ref "C8") (pin "2") (pinfunction "2_2") (pintype "unspecified"))
      (node (ref "C80") (pin "1") (pinfunction "1_1") (pintype "input"))
      (node (ref "C81") (pin "1") (pinfunction "1_1") (pintype "input"))
      (node (ref "C82") (pin "1") (pinfunction "1_1") (pintype "unspecified"))
      (node (ref "C83") (pin "1") (pinfunction "1_1") (pintype "unspecified"))
      (node (ref "DEBUG") (pin "1") (pinfunction "1_1") (pintype "unspecified"))
      (node (ref "Q1") (pin "2") (pinfunction "S_2") (pintype "unspecified"))
      (node (ref "R17") (pin "1") (pinfunction "1_1") (pintype "unspecified"))
      (node (ref "R3") (pin "2") (pinfunction "2_2") (pintype "unspecified"))
      (node (ref "R7") (pin "2") (pinfunction "2_2") (pintype "unspecified"))
      (node (ref "R8") (pin "2") (pinfunction "2_2") (pintype "unspecified"))
      (node (ref "U1") (pin "12") (pinfunction "VSSA_12") (pintype "unspecified"))
      (node (ref "U1") (pin "18") (pinfunction "VSS_18") (pintype "unspecified"))
      (node (ref "U1") (pin "31") (pinfunction "VSS_31") (pintype "unspecified"))
      (node (ref "U1") (pin "47") (pinfunction "VSS_47") (pintype "unspecified"))
      (node (ref "U1") (pin "63") (pinfunction "VSS_63") (pintype "unspecified"))
      (node (ref "U16") (pin "4") (pinfunction "GND_4") (pintype "unspecified"))
      (node (ref "U17") (pin "1") (pinfunction "K_1") (pintype "unspecified"))
      (node (ref "U18") (pin "2") (pinfunction "-_2") (pintype "unspecified"))
      (node (ref "U8") (pin "10") (pinfunction "LSS_10") (pintype "unspecified"))
      (node (ref "U8") (pin "12") (pinfunction "LSS_12") (pintype "unspecified"))
      (node (ref "U8") (pin "18") (pinfunction "GND_18") (pintype "unspecified"))
      (node (ref "U9") (pin "10") (pinfunction "LSS_10") (pintype "unspecified"))
      (node (ref "U9") (pin "12") (pinfunction "LSS_12") (pintype "unspecified"))
      (node (ref "U9") (pin "18") (pinfunction "GND_18") (pintype "unspecified"))
      (node (ref "USB1") (pin "1") (pinfunction "SHELL_1") (pintype "unspecified"))
      (node (ref "USB1") (pin "2") (pinfunction "SHELL_2") (pintype "unspecified"))
      (node (ref "USB1") (pin "3") (pinfunction "SHELL_3") (pintype "unspecified"))
      (node (ref "USB1") (pin "4") (pinfunction "SHELL_4") (pintype "unspecified"))
      (node (ref "USB1") (pin "A1B12") (pinfunction "GND_A1B12") (pintype "unspecified"))
      (node (ref "USB1") (pin "B1A12") (pinfunction "GND_B1A12") (pintype "unspecified"))
      (node (ref "accu") (pin "1") (pinfunction "1_1") (pintype "unspecified"))
      (node (ref "imu") (pin "P$1") (pinfunction "SDO/SA0_P$1") (pintype "bidirectional"))
      (node (ref "imu") (pin "P$2") (pinfunction "SDX_P$2") (pintype "bidirectional"))
      (node (ref "imu") (pin "P$3") (pinfunction "SCX_P$3") (pintype "bidirectional"))
      (node (ref "imu") (pin "P$6") (pinfunction "GND1_P$6") (pintype "bidirectional"))
      (node (ref "imu") (pin "P$7") (pinfunction "GND2_P$7") (pintype "bidirectional"))
      (node (ref "key0") (pin "3") (pinfunction "3_3") (pintype "unspecified"))
      (node (ref "key1") (pin "3") (pinfunction "3_3") (pintype "unspecified"))
      (node (ref "left_encoder") (pin "4") (pinfunction "4_4") (pintype "input"))
      (node (ref "line_sensor") (pin "5") (pinfunction "5_5") (pintype "unspecified"))
      (node (ref "line_sensor") (pin "6") (pinfunction "6_6") (pintype "unspecified"))
      (node (ref "line_sensor") (pin "7") (pinfunction "7_7") (pintype "unspecified"))
      (node (ref "reset") (pin "3") (pinfunction "3_3") (pintype "unspecified"))
      (node (ref "right_encoder") (pin "4") (pinfunction "4_4") (pintype "input"))
      (node (ref "turbine") (pin "3") (pinfunction "3_3") (pintype "input"))
    )
    (net (code "8") (name "KEY0") (class "Default")
      (node (ref "U1") (pin "27") (pinfunction "PB2_27") (pintype "unspecified"))
      (node (ref "key0") (pin "2") (pinfunction "2_2") (pintype "unspecified"))
    )
    (net (code "9") (name "KEY1") (class "Default")
      (node (ref "U1") (pin "26") (pinfunction "PB1_26") (pintype "unspecified"))
      (node (ref "key1") (pin "2") (pinfunction "2_2") (pintype "unspecified"))
    )
    (net (code "10") (name "LE") (class "Default")
      (node (ref "U1") (pin "40") (pinfunction "PC9_40") (pintype "unspecified"))
      (node (ref "U8") (pin "3") (pinfunction "ENA_3") (pintype "unspecified"))
      (node (ref "U8") (pin "4") (pinfunction "ENB_4") (pintype "unspecified"))
      (node (ref "U8") (pin "5") (pinfunction "ENC_5") (pintype "unspecified"))
    )
    (net (code "11") (name "LED0") (class "Default")
      (node (ref "R4") (pin "2") (pinfunction "2_2") (pintype "unspecified"))
      (node (ref "U1") (pin "25") (pinfunction "PB0_25") (pintype "unspecified"))
    )
    (net (code "12") (name "LED1") (class "Default")
      (node (ref "R5") (pin "2") (pinfunction "2_2") (pintype "unspecified"))
      (node (ref "U1") (pin "24") (pinfunction "PC4_24") (pintype "unspecified"))
    )
    (net (code "13") (name "LED2") (class "Default")
      (node (ref "R6") (pin "2") (pinfunction "2_2") (pintype "unspecified"))
      (node (ref "U1") (pin "23") (pinfunction "PA7_23") (pintype "unspecified"))
    )
    (net (code "14") (name "LED3") (class "Default")
      (node (ref "R13") (pin "2") (pinfunction "2_2") (pintype "unspecified"))
      (node (ref "U1") (pin "14") (pinfunction "PA0-WKUP_14") (pintype "unspecified"))
    )
    (net (code "15") (name "LED4") (class "Default")
      (node (ref "R14") (pin "2") (pinfunction "2_2") (pintype "unspecified"))
      (node (ref "U1") (pin "15") (pinfunction "PA1_15") (pintype "unspecified"))
    )
    (net (code "16") (name "LED5") (class "Default")
      (node (ref "R15") (pin "2") (pinfunction "2_2") (pintype "unspecified"))
      (node (ref "U1") (pin "16") (pinfunction "PA2_16") (pintype "unspecified"))
    )
    (net (code "17") (name "LS_RESET") (class "Default")
      (node (ref "U1") (pin "17") (pinfunction "PA3_17") (pintype "unspecified"))
      (node (ref "line_sensor") (pin "4") (pinfunction "4_4") (pintype "unspecified"))
    )
    (net (code "18") (name "LS_SCL") (class "Default")
      (node (ref "U1") (pin "20") (pinfunction "PA4_20") (pintype "unspecified"))
      (node (ref "line_sensor") (pin "2") (pinfunction "2_2") (pintype "unspecified"))
    )
    (net (code "19") (name "LS_SDA") (class "Default")
      (node (ref "U1") (pin "21") (pinfunction "PA5_21") (pintype "unspecified"))
      (node (ref "line_sensor") (pin "3") (pinfunction "3_3") (pintype "unspecified"))
    )
    (net (code "20") (name "L_SCL") (class "Default")
      (node (ref "U1") (pin "11") (pinfunction "PC3_11") (pintype "unspecified"))
    )
    (net (code "21") (name "L_SDA") (class "Default")
      (node (ref "U1") (pin "10") (pinfunction "PC2_10") (pintype "unspecified"))
    )
    (net (code "22") (name "MLA") (class "Default")
      (node (ref "C76") (pin "2") (pinfunction "2_2") (pintype "input"))
      (node (ref "U8") (pin "26") (pinfunction "SA_26") (pintype "unspecified"))
      (node (ref "U8") (pin "9") (pinfunction "SA_9") (pintype "unspecified"))
      (node (ref "motor_left") (pin "1") (pinfunction "1_1") (pintype "input"))
    )
    (net (code "23") (name "MLB") (class "Default")
      (node (ref "C77") (pin "2") (pinfunction "2_2") (pintype "input"))
      (node (ref "U8") (pin "11") (pinfunction "SB_11") (pintype "unspecified"))
      (node (ref "U8") (pin "24") (pinfunction "SB_24") (pintype "unspecified"))
      (node (ref "motor_left") (pin "2") (pinfunction "2_2") (pintype "input"))
    )
    (net (code "24") (name "MLC") (class "Default")
      (node (ref "C78") (pin "2") (pinfunction "2_2") (pintype "input"))
      (node (ref "U8") (pin "13") (pinfunction "SC_13") (pintype "unspecified"))
      (node (ref "U8") (pin "22") (pinfunction "SC_22") (pintype "unspecified"))
      (node (ref "motor_left") (pin "3") (pinfunction "3_3") (pintype "input"))
    )
    (net (code "25") (name "MRA") (class "Default")
      (node (ref "C79") (pin "2") (pinfunction "2_2") (pintype "input"))
      (node (ref "U9") (pin "26") (pinfunction "SA_26") (pintype "unspecified"))
      (node (ref "U9") (pin "9") (pinfunction "SA_9") (pintype "unspecified"))
      (node (ref "motor_right") (pin "1") (pinfunction "1_1") (pintype "input"))
    )
    (net (code "26") (name "MRB") (class "Default")
      (node (ref "C80") (pin "2") (pinfunction "2_2") (pintype "input"))
      (node (ref "U9") (pin "11") (pinfunction "SB_11") (pintype "unspecified"))
      (node (ref "U9") (pin "24") (pinfunction "SB_24") (pintype "unspecified"))
      (node (ref "motor_right") (pin "2") (pinfunction "2_2") (pintype "input"))
    )
    (net (code "27") (name "MRC") (class "Default")
      (node (ref "C81") (pin "2") (pinfunction "2_2") (pintype "input"))
      (node (ref "U9") (pin "13") (pinfunction "SC_13") (pintype "unspecified"))
      (node (ref "U9") (pin "22") (pinfunction "SC_22") (pintype "unspecified"))
      (node (ref "motor_right") (pin "3") (pinfunction "3_3") (pintype "input"))
    )
    (net (code "28") (name "Net-(Q1-D)") (class "Default")
      (node (ref "Q1") (pin "3") (pinfunction "D_3") (pintype "unspecified"))
      (node (ref "R16") (pin "1") (pinfunction "1_1") (pintype "unspecified"))
      (node (ref "turbine") (pin "1") (pinfunction "1_1") (pintype "input"))
    )
    (net (code "29") (name "Net-(R4-Pad1)") (class "Default")
      (node (ref "R4") (pin "1") (pinfunction "1_1") (pintype "unspecified"))
      (node (ref "U4") (pin "2") (pinfunction "C_2") (pintype "unspecified"))
    )
    (net (code "30") (name "Net-(R5-Pad1)") (class "Default")
      (node (ref "R5") (pin "1") (pinfunction "1_1") (pintype "unspecified"))
      (node (ref "U4") (pin "3") (pinfunction "C_3") (pintype "unspecified"))
    )
    (net (code "31") (name "Net-(R6-Pad1)") (class "Default")
      (node (ref "R6") (pin "1") (pinfunction "1_1") (pintype "unspecified"))
      (node (ref "U4") (pin "4") (pinfunction "C_4") (pintype "unspecified"))
    )
    (net (code "32") (name "Net-(R13-Pad1)") (class "Default")
      (node (ref "R13") (pin "1") (pinfunction "1_1") (pintype "unspecified"))
      (node (ref "U5") (pin "2") (pinfunction "C_2") (pintype "unspecified"))
    )
    (net (code "33") (name "Net-(R14-Pad1)") (class "Default")
      (node (ref "R14") (pin "1") (pinfunction "1_1") (pintype "unspecified"))
      (node (ref "U5") (pin "3") (pinfunction "C_3") (pintype "unspecified"))
    )
    (net (code "34") (name "Net-(R15-Pad1)") (class "Default")
      (node (ref "R15") (pin "1") (pinfunction "1_1") (pintype "unspecified"))
      (node (ref "U5") (pin "4") (pinfunction "C_4") (pintype "unspecified"))
    )
    (net (code "35") (name "Net-(U1-PH0-OSC_IN)") (class "Default")
      (node (ref "C82") (pin "2") (pinfunction "2_2") (pintype "unspecified"))
      (node (ref "U1") (pin "5") (pinfunction "PH0-OSC_IN_5") (pintype "unspecified"))
      (node (ref "X1") (pin "3") (pinfunction "OSC2_3") (pintype "unspecified"))
    )
    (net (code "36") (name "Net-(U1-PH1-OSC_OUT)") (class "Default")
      (node (ref "C83") (pin "2") (pinfunction "2_2") (pintype "unspecified"))
      (node (ref "U1") (pin "6") (pinfunction "PH1-OSC_OUT_6") (pintype "unspecified"))
      (node (ref "X1") (pin "1") (pinfunction "OSC1_1") (pintype "unspecified"))
    )
    (net (code "37") (name "Net-(U1-VCAP_1)") (class "Default")
      (node (ref "C8") (pin "1") (pinfunction "1_1") (pintype "unspecified"))
      (node (ref "U1") (pin "30") (pinfunction "VCAP_1_30") (pintype "unspecified"))
    )
    (net (code "38") (name "Net-(U8-CP1)") (class "Default")
      (node (ref "C13") (pin "2") (pinfunction "2_2") (pintype "unspecified"))
      (node (ref "U8") (pin "20") (pinfunction "CP1_20") (pintype "unspecified"))
    )
    (net (code "39") (name "Net-(U8-CP2)") (class "Default")
      (node (ref "C13") (pin "1") (pinfunction "1_1") (pintype "unspecified"))
      (node (ref "U8") (pin "21") (pinfunction "CP2_21") (pintype "unspecified"))
    )
    (net (code "40") (name "Net-(U8-VCP)") (class "Default")
      (node (ref "C15") (pin "2") (pinfunction "2_2") (pintype "unspecified"))
      (node (ref "U8") (pin "19") (pinfunction "VCP_19") (pintype "unspecified"))
    )
    (net (code "41") (name "Net-(U8-VG)") (class "Default")
      (node (ref "C14") (pin "2") (pinfunction "2_2") (pintype "input"))
      (node (ref "U8") (pin "14") (pinfunction "VG_14") (pintype "unspecified"))
    )
    (net (code "42") (name "Net-(U9-CP1)") (class "Default")
      (node (ref "C19") (pin "2") (pinfunction "2_2") (pintype "unspecified"))
      (node (ref "U9") (pin "20") (pinfunction "CP1_20") (pintype "unspecified"))
    )
    (net (code "43") (name "Net-(U9-CP2)") (class "Default")
      (node (ref "C19") (pin "1") (pinfunction "1_1") (pintype "unspecified"))
      (node (ref "U9") (pin "21") (pinfunction "CP2_21") (pintype "unspecified"))
    )
    (net (code "44") (name "Net-(U9-VCP)") (class "Default")
      (node (ref "C21") (pin "2") (pinfunction "2_2") (pintype "unspecified"))
      (node (ref "U9") (pin "19") (pinfunction "VCP_19") (pintype "unspecified"))
    )
    (net (code "45") (name "Net-(U9-VG)") (class "Default")
      (node (ref "C20") (pin "2") (pinfunction "2_2") (pintype "input"))
      (node (ref "U9") (pin "14") (pinfunction "VG_14") (pintype "unspecified"))
    )
    (net (code "46") (name "Net-(U16-BST)") (class "Default")
      (node (ref "C62") (pin "2") (pinfunction "2_2") (pintype "unspecified"))
      (node (ref "U16") (pin "6") (pinfunction "BST_6") (pintype "unspecified"))
    )
    (net (code "47") (name "Net-(U16-SW)") (class "Default")
      (node (ref "C62") (pin "1") (pinfunction "1_1") (pintype "unspecified"))
      (node (ref "L1") (pin "1") (pinfunction "1_1") (pintype "unspecified"))
      (node (ref "U16") (pin "5") (pinfunction "SW_5") (pintype "unspecified"))
    )
    (net (code "48") (name "Net-(U17-A)") (class "Default")
      (node (ref "R1") (pin "1") (pinfunction "1_1") (pintype "input"))
      (node (ref "U17") (pin "2") (pinfunction "A_2") (pintype "unspecified"))
    )
    (net (code "49") (name "Net-(U18-+)") (class "Default")
      (node (ref "R18") (pin "2") (pinfunction "2_2") (pintype "input"))
      (node (ref "U18") (pin "1") (pinfunction "+_1") (pintype "unspecified"))
    )
    (net (code "50") (name "Net-(USB1-CC1)") (class "Default")
      (node (ref "R8") (pin "1") (pinfunction "1_1") (pintype "unspecified"))
      (node (ref "USB1") (pin "A5") (pinfunction "CC1_A5") (pintype "unspecified"))
    )
    (net (code "51") (name "Net-(USB1-CC2)") (class "Default")
      (node (ref "R7") (pin "1") (pinfunction "1_1") (pintype "unspecified"))
      (node (ref "USB1") (pin "B5") (pinfunction "CC2_B5") (pintype "unspecified"))
    )
    (net (code "52") (name "PLA") (class "Default")
      (node (ref "U1") (pin "37") (pinfunction "PC6_37") (pintype "unspecified"))
      (node (ref "U8") (pin "6") (pinfunction "PWMA_6") (pintype "unspecified"))
    )
    (net (code "53") (name "PLB") (class "Default")
      (node (ref "U1") (pin "38") (pinfunction "PC7_38") (pintype "unspecified"))
      (node (ref "U8") (pin "7") (pinfunction "PWMB_7") (pintype "unspecified"))
    )
    (net (code "54") (name "PLC") (class "Default")
      (node (ref "U1") (pin "39") (pinfunction "PC8_39") (pintype "unspecified"))
      (node (ref "U8") (pin "8") (pinfunction "PWMC_8") (pintype "unspecified"))
    )
    (net (code "55") (name "PRA") (class "Default")
      (node (ref "U1") (pin "58") (pinfunction "PB6_58") (pintype "unspecified"))
      (node (ref "U9") (pin "6") (pinfunction "PWMA_6") (pintype "unspecified"))
    )
    (net (code "56") (name "PRB") (class "Default")
      (node (ref "U1") (pin "59") (pinfunction "PB7_59") (pintype "unspecified"))
      (node (ref "U9") (pin "7") (pinfunction "PWMB_7") (pintype "unspecified"))
    )
    (net (code "57") (name "PRC") (class "Default")
      (node (ref "U1") (pin "61") (pinfunction "PB8_61") (pintype "unspecified"))
      (node (ref "U9") (pin "8") (pinfunction "PWMC_8") (pintype "unspecified"))
    )
    (net (code "58") (name "RE") (class "Default")
      (node (ref "U1") (pin "62") (pinfunction "PB9_62") (pintype "unspecified"))
      (node (ref "U9") (pin "3") (pinfunction "ENA_3") (pintype "unspecified"))
      (node (ref "U9") (pin "4") (pinfunction "ENB_4") (pintype "unspecified"))
      (node (ref "U9") (pin "5") (pinfunction "ENC_5") (pintype "unspecified"))
    )
    (net (code "59") (name "RESET") (class "Default")
      (node (ref "C68") (pin "2") (pinfunction "2_2") (pintype "unspecified"))
      (node (ref "DEBUG") (pin "4") (pinfunction "4_4") (pintype "unspecified"))
      (node (ref "R2") (pin "1") (pinfunction "1_1") (pintype "unspecified"))
      (node (ref "U1") (pin "7") (pinfunction "NRST_7") (pintype "unspecified"))
      (node (ref "reset") (pin "2") (pinfunction "2_2") (pintype "unspecified"))
    )
    (net (code "60") (name "SCL") (class "Default")
      (node (ref "U1") (pin "35") (pinfunction "PB14_35") (pintype "unspecified"))
      (node (ref "imu") (pin "P$13") (pinfunction "SCL_P$13") (pintype "bidirectional"))
    )
    (net (code "61") (name "SDA") (class "Default")
      (node (ref "U1") (pin "36") (pinfunction "PB15_36") (pintype "unspecified"))
      (node (ref "imu") (pin "P$14") (pinfunction "SDA_P$14") (pintype "bidirectional"))
    )
    (net (code "62") (name "SPEAKER") (class "Default")
      (node (ref "R18") (pin "1") (pinfunction "1_1") (pintype "input"))
      (node (ref "U1") (pin "22") (pinfunction "PA6_22") (pintype "unspecified"))
    )
    (net (code "63") (name "SWCLK") (class "Default")
      (node (ref "DEBUG") (pin "8") (pinfunction "8_8") (pintype "unspecified"))
      (node (ref "U1") (pin "49") (pinfunction "PA14_49") (pintype "unspecified"))
    )
    (net (code "64") (name "SWDIO") (class "Default")
      (node (ref "DEBUG") (pin "6") (pinfunction "6_6") (pintype "unspecified"))
      (node (ref "U1") (pin "46") (pinfunction "PA13_46") (pintype "unspecified"))
    )
    (net (code "65") (name "SWO") (class "Default")
      (node (ref "DEBUG") (pin "2") (pinfunction "2_2") (pintype "unspecified"))
      (node (ref "U1") (pin "55") (pinfunction "PB3_55") (pintype "unspecified"))
    )
    (net (code "66") (name "TPWM") (class "Default")
      (node (ref "Q1") (pin "1") (pinfunction "G_1") (pintype "unspecified"))
      (node (ref "R17") (pin "2") (pinfunction "2_2") (pintype "unspecified"))
      (node (ref "U1") (pin "28") (pinfunction "PB10_28") (pintype "unspecified"))
    )
    (net (code "67") (name "UART_RX") (class "Default")
      (node (ref "DEBUG") (pin "3") (pinfunction "3_3") (pintype "unspecified"))
      (node (ref "U1") (pin "43") (pinfunction "PA10_43") (pintype "unspecified"))
    )
    (net (code "68") (name "UART_TX") (class "Default")
      (node (ref "DEBUG") (pin "5") (pinfunction "5_5") (pintype "unspecified"))
      (node (ref "U1") (pin "42") (pinfunction "PA9_42") (pintype "unspecified"))
    )
    (net (code "69") (name "USB_DN") (class "Default")
      (node (ref "U1") (pin "44") (pinfunction "PA11_44") (pintype "unspecified"))
      (node (ref "USB1") (pin "A7") (pinfunction "DN1_A7") (pintype "unspecified"))
      (node (ref "USB1") (pin "B7") (pinfunction "DN2_B7") (pintype "unspecified"))
    )
    (net (code "70") (name "USB_DP") (class "Default")
      (node (ref "U1") (pin "45") (pinfunction "PA12_45") (pintype "unspecified"))
      (node (ref "USB1") (pin "A6") (pinfunction "DP1_A6") (pintype "unspecified"))
      (node (ref "USB1") (pin "B6") (pinfunction "DP2_B6") (pintype "unspecified"))
    )
    (net (code "71") (name "VBAT") (class "Default")
      (node (ref "C11") (pin "2") (pinfunction "2_2") (pintype "unspecified"))
      (node (ref "C12") (pin "2") (pinfunction "2_2") (pintype "unspecified"))
      (node (ref "C15") (pin "1") (pinfunction "1_1") (pintype "unspecified"))
      (node (ref "C16") (pin "2") (pinfunction "2_2") (pintype "unspecified"))
      (node (ref "C17") (pin "2") (pinfunction "2_2") (pintype "unspecified"))
      (node (ref "C18") (pin "2") (pinfunction "2_2") (pintype "unspecified"))
      (node (ref "C21") (pin "1") (pinfunction "1_1") (pintype "unspecified"))
      (node (ref "C22") (pin "2") (pinfunction "2_2") (pintype "unspecified"))
      (node (ref "C66") (pin "2") (pinfunction "2_2") (pintype "unspecified"))
      (node (ref "C67") (pin "2") (pinfunction "2_2") (pintype "unspecified"))
      (node (ref "C74") (pin "1") (pinfunction "1_1") (pintype "input"))
      (node (ref "C75") (pin "1") (pinfunction "1_1") (pintype "input"))
      (node (ref "D1") (pin "1") (pinfunction "K_1") (pintype "unspecified"))
      (node (ref "R16") (pin "2") (pinfunction "2_2") (pintype "unspecified"))
      (node (ref "U16") (pin "2") (pinfunction "EN_2") (pintype "unspecified"))
      (node (ref "U16") (pin "3") (pinfunction "VIN_3") (pintype "unspecified"))
      (node (ref "U8") (pin "23") (pinfunction "VIN_23") (pintype "unspecified"))
      (node (ref "U8") (pin "25") (pinfunction "VIN_25") (pintype "unspecified"))
      (node (ref "U9") (pin "23") (pinfunction "VIN_23") (pintype "unspecified"))
      (node (ref "U9") (pin "25") (pinfunction "VIN_25") (pintype "unspecified"))
      (node (ref "accu") (pin "2") (pinfunction "2_2") (pintype "unspecified"))
      (node (ref "turbine") (pin "2") (pinfunction "2_2") (pintype "input"))
    )
    (net (code "72") (name "VBUS") (class "Default")
      (node (ref "D1") (pin "2") (pinfunction "A_2") (pintype "unspecified"))
      (node (ref "USB1") (pin "A4B9") (pinfunction "VBUS_A4B9") (pintype "unspecified"))
      (node (ref "USB1") (pin "B4A9") (pinfunction "VBUS_B4A9") (pintype "unspecified"))
    )
    (net (code "73") (name "unconnected-(U1-PA8-Pad41)") (class "Default")
      (node (ref "U1") (pin "41") (pinfunction "PA8_41") (pintype "unspecified"))
    )
    (net (code "74") (name "unconnected-(U1-PA15-Pad50)") (class "Default")
      (node (ref "U1") (pin "50") (pinfunction "PA15_50") (pintype "unspecified"))
    )
    (net (code "75") (name "unconnected-(U1-PB4-Pad56)") (class "Default")
      (node (ref "U1") (pin "56") (pinfunction "PB4_56") (pintype "unspecified"))
    )
    (net (code "76") (name "unconnected-(U1-PB5-Pad57)") (class "Default")
      (node (ref "U1") (pin "57") (pinfunction "PB5_57") (pintype "unspecified"))
    )
    (net (code "77") (name "unconnected-(U1-PB11-Pad29)") (class "Default")
      (node (ref "U1") (pin "29") (pinfunction "PB11_29") (pintype "unspecified"))
    )
    (net (code "78") (name "unconnected-(U1-PC0-Pad8)") (class "Default")
      (node (ref "U1") (pin "8") (pinfunction "PC0_8") (pintype "unspecified"))
    )
    (net (code "79") (name "unconnected-(U1-PC1-Pad9)") (class "Default")
      (node (ref "U1") (pin "9") (pinfunction "PC1_9") (pintype "unspecified"))
    )
    (net (code "80") (name "unconnected-(U1-PC12-Pad53)") (class "Default")
      (node (ref "U1") (pin "53") (pinfunction "PC12_53") (pintype "unspecified"))
    )
    (net (code "81") (name "unconnected-(U1-PC13-Pad2)") (class "Default")
      (node (ref "U1") (pin "2") (pinfunction "PC13_2") (pintype "unspecified"))
    )
    (net (code "82") (name "unconnected-(U1-PC14-OSC32_IN-Pad3)") (class "Default")
      (node (ref "U1") (pin "3") (pinfunction "PC14-OSC32_IN_3") (pintype "unspecified"))
    )
    (net (code "83") (name "unconnected-(U1-PC15-OSC32_OUT-Pad4)") (class "Default")
      (node (ref "U1") (pin "4") (pinfunction "PC15-OSC32_OUT_4") (pintype "unspecified"))
    )
    (net (code "84") (name "unconnected-(U1-PD2-Pad54)") (class "Default")
      (node (ref "U1") (pin "54") (pinfunction "PD2_54") (pintype "unspecified"))
    )
    (net (code "85") (name "unconnected-(U1-VBAT-Pad1)") (class "Default")
      (node (ref "U1") (pin "1") (pinfunction "VBAT_1") (pintype "unspecified"))
    )
    (net (code "86") (name "unconnected-(U8-SOA-Pad15)") (class "Default")
      (node (ref "U8") (pin "15") (pinfunction "SOA_15") (pintype "unspecified"))
    )
    (net (code "87") (name "unconnected-(U8-SOB-Pad16)") (class "Default")
      (node (ref "U8") (pin "16") (pinfunction "SOB_16") (pintype "unspecified"))
    )
    (net (code "88") (name "unconnected-(U8-SOC-Pad17)") (class "Default")
      (node (ref "U8") (pin "17") (pinfunction "SOC_17") (pintype "unspecified"))
    )
    (net (code "89") (name "unconnected-(U8-nFAULT-Pad1)") (class "Default")
      (node (ref "U8") (pin "1") (pinfunction "nFAULT_1") (pintype "unspecified"))
    )
    (net (code "90") (name "unconnected-(U9-SOA-Pad15)") (class "Default")
      (node (ref "U9") (pin "15") (pinfunction "SOA_15") (pintype "unspecified"))
    )
    (net (code "91") (name "unconnected-(U9-SOB-Pad16)") (class "Default")
      (node (ref "U9") (pin "16") (pinfunction "SOB_16") (pintype "unspecified"))
    )
    (net (code "92") (name "unconnected-(U9-SOC-Pad17)") (class "Default")
      (node (ref "U9") (pin "17") (pinfunction "SOC_17") (pintype "unspecified"))
    )
    (net (code "93") (name "unconnected-(U9-nFAULT-Pad1)") (class "Default")
      (node (ref "U9") (pin "1") (pinfunction "nFAULT_1") (pintype "unspecified"))
    )
    (net (code "94") (name "unconnected-(USB1-SBU1-PadA8)") (class "Default")
      (node (ref "USB1") (pin "A8") (pinfunction "SBU1_A8") (pintype "unspecified"))
    )
    (net (code "95") (name "unconnected-(USB1-SBU2-PadB8)") (class "Default")
      (node (ref "USB1") (pin "B8") (pinfunction "SBU2_B8") (pintype "unspecified"))
    )
    (net (code "96") (name "unconnected-(X1-GND-Pad2)") (class "Default")
      (node (ref "X1") (pin "2") (pinfunction "GND_2") (pintype "unspecified"))
    )
    (net (code "97") (name "unconnected-(X1-GND-Pad4)") (class "Default")
      (node (ref "X1") (pin "4") (pinfunction "GND_4") (pintype "unspecified"))
    )
    (net (code "98") (name "unconnected-(imu-INT1-PadP$4)") (class "Default")
      (node (ref "imu") (pin "P$4") (pinfunction "INT1_P$4") (pintype "bidirectional"))
    )
    (net (code "99") (name "unconnected-(imu-INT2-PadP$9)") (class "Default")
      (node (ref "imu") (pin "P$9") (pinfunction "INT2_P$9") (pintype "bidirectional"))
    )
    (net (code "100") (name "unconnected-(imu-NC1-PadP$10)") (class "Default")
      (node (ref "imu") (pin "P$10") (pinfunction "NC1_P$10") (pintype "bidirectional"))
    )
    (net (code "101") (name "unconnected-(imu-NC2-PadP$11)") (class "Default")
      (node (ref "imu") (pin "P$11") (pinfunction "NC2_P$11") (pintype "bidirectional"))
    )
    (net (code "102") (name "unconnected-(key0-Pad1)") (class "Default")
      (node (ref "key0") (pin "1") (pinfunction "1_1") (pintype "unspecified"))
    )
    (net (code "103") (name "unconnected-(key0-Pad4)") (class "Default")
      (node (ref "key0") (pin "4") (pinfunction "4_4") (pintype "unspecified"))
    )
    (net (code "104") (name "unconnected-(key1-Pad1)") (class "Default")
      (node (ref "key1") (pin "1") (pinfunction "1_1") (pintype "unspecified"))
    )
    (net (code "105") (name "unconnected-(key1-Pad4)") (class "Default")
      (node (ref "key1") (pin "4") (pinfunction "4_4") (pintype "unspecified"))
    )
    (net (code "106") (name "unconnected-(reset-Pad1)") (class "Default")
      (node (ref "reset") (pin "1") (pinfunction "1_1") (pintype "unspecified"))
    )
    (net (code "107") (name "unconnected-(reset-Pad4)") (class "Default")
      (node (ref "reset") (pin "4") (pinfunction "4_4") (pintype "unspecified"))
    )
  )
)
